# transponder-10_9_0.net
KiCad netlist of a schematic drawn in EAGLE
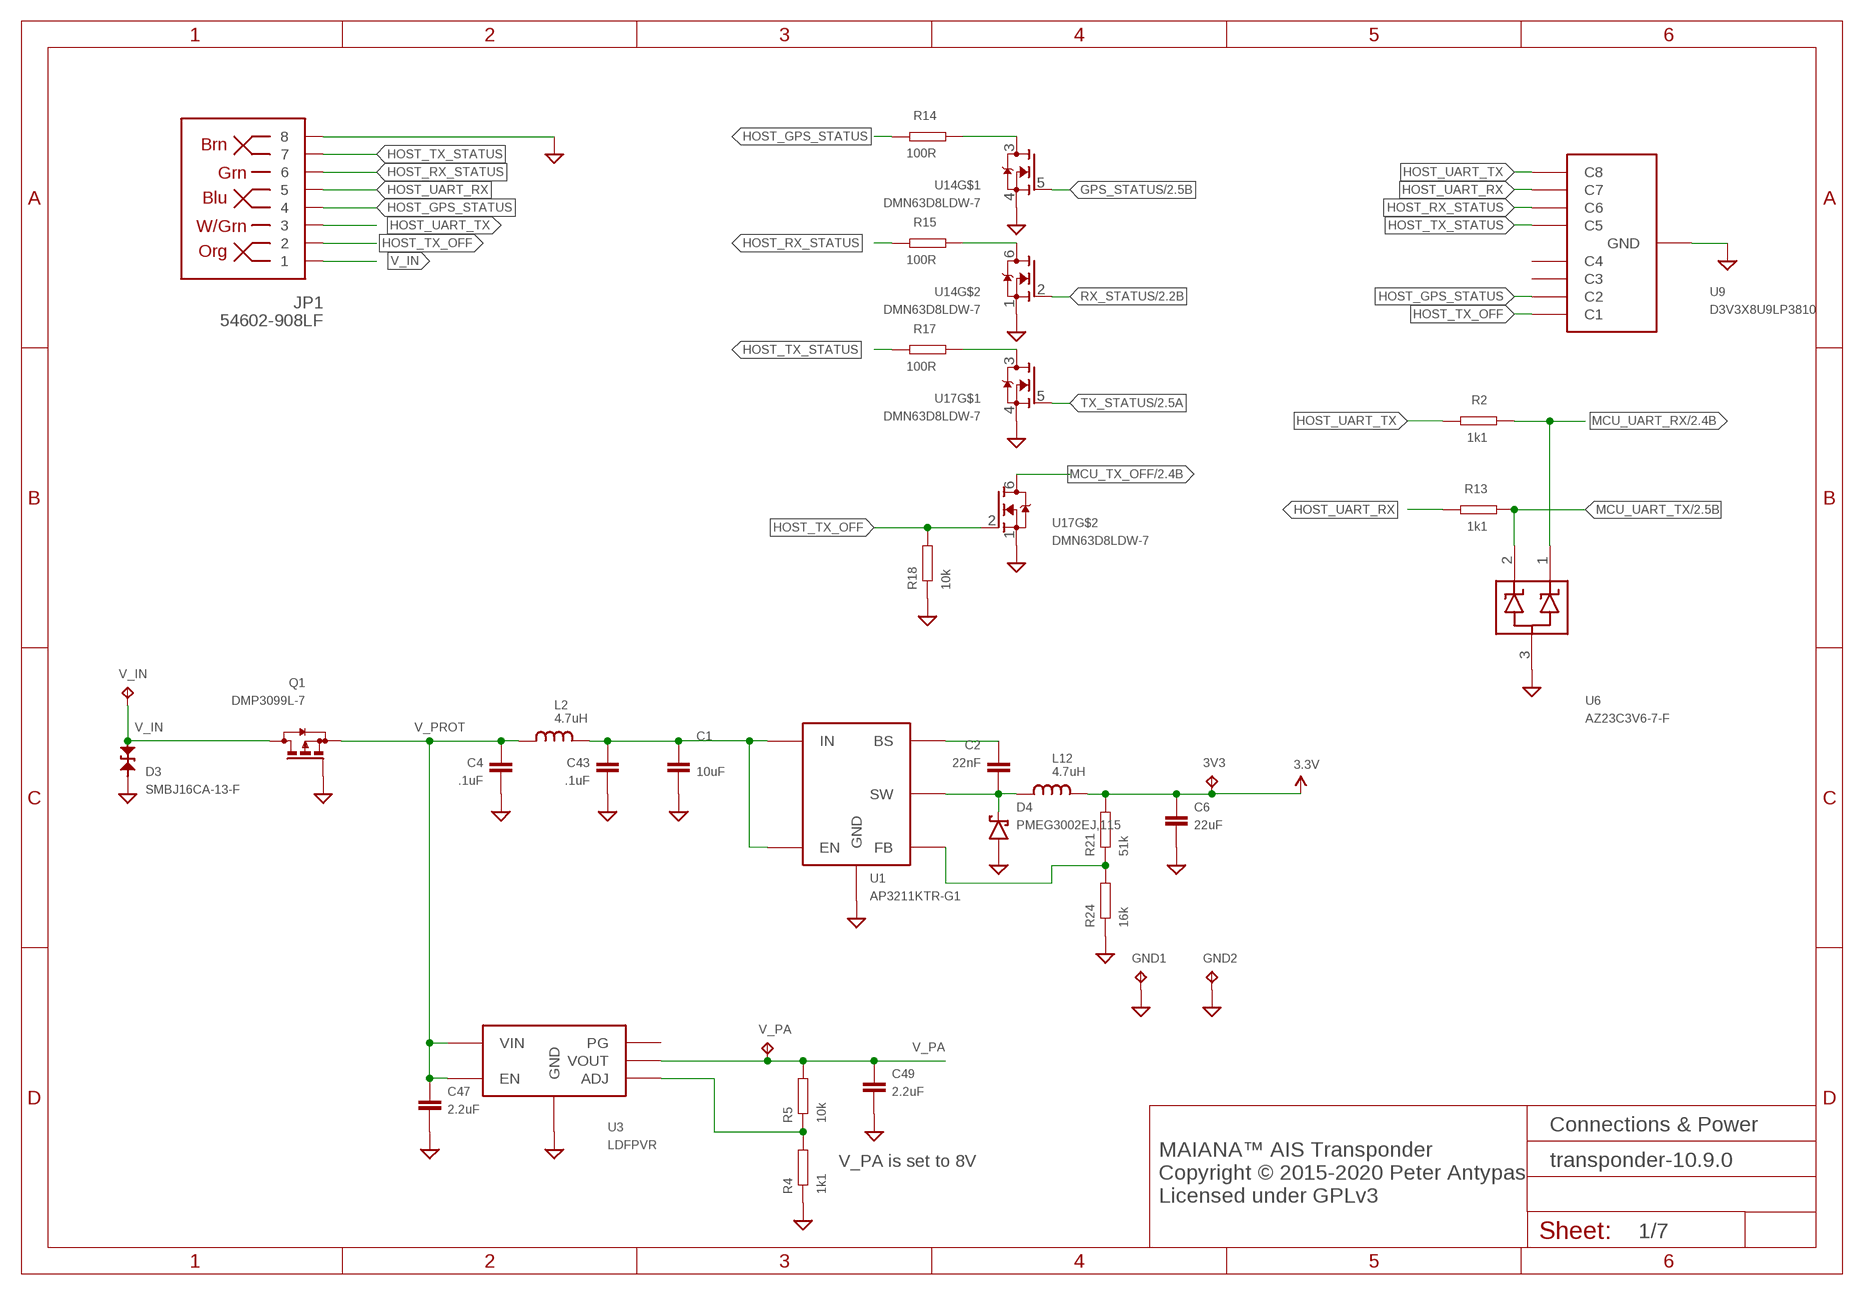
[diagram p0: schematic, sheet 1]
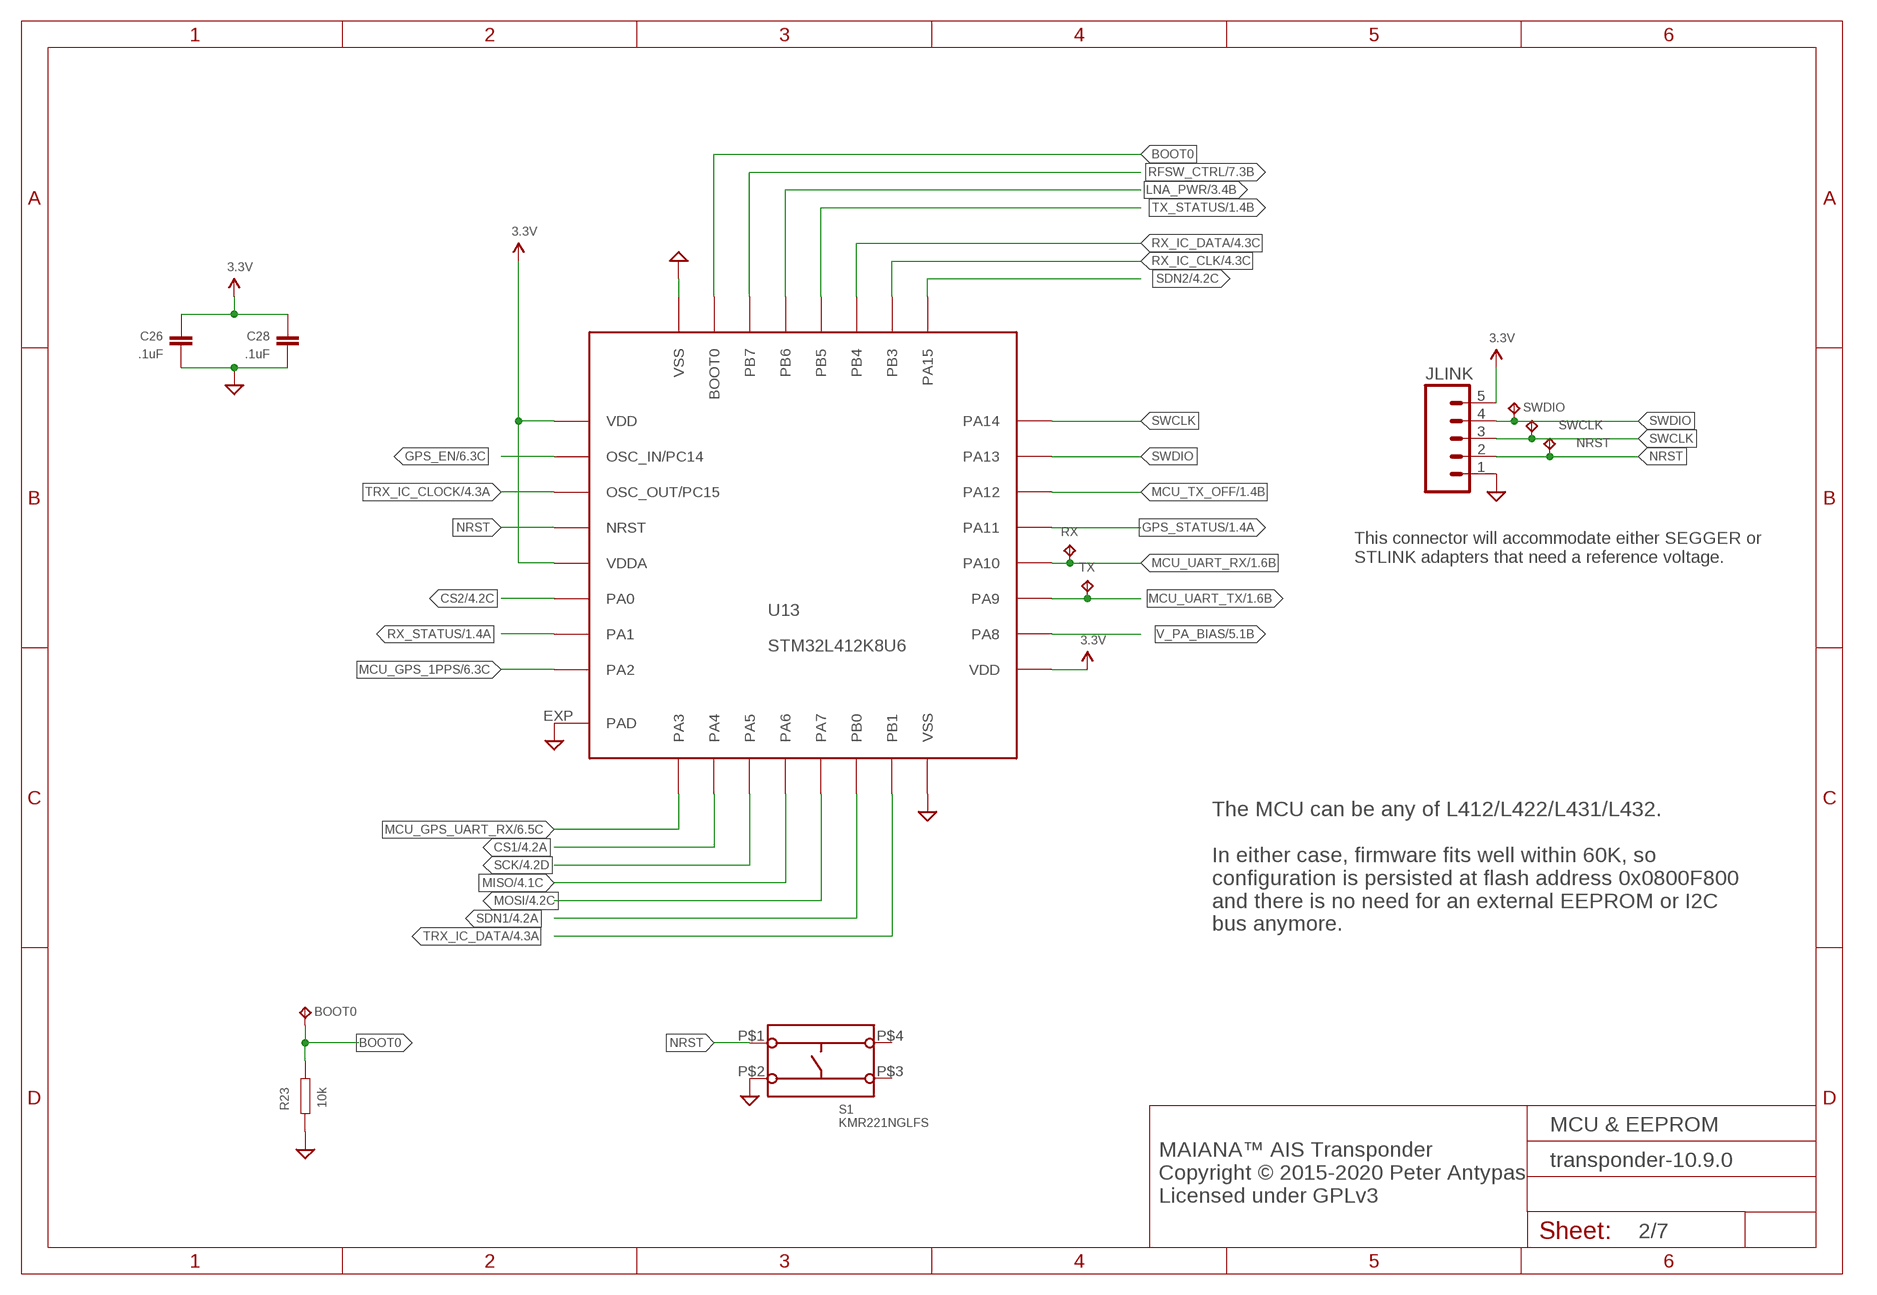
[diagram p1: schematic, sheet 2]
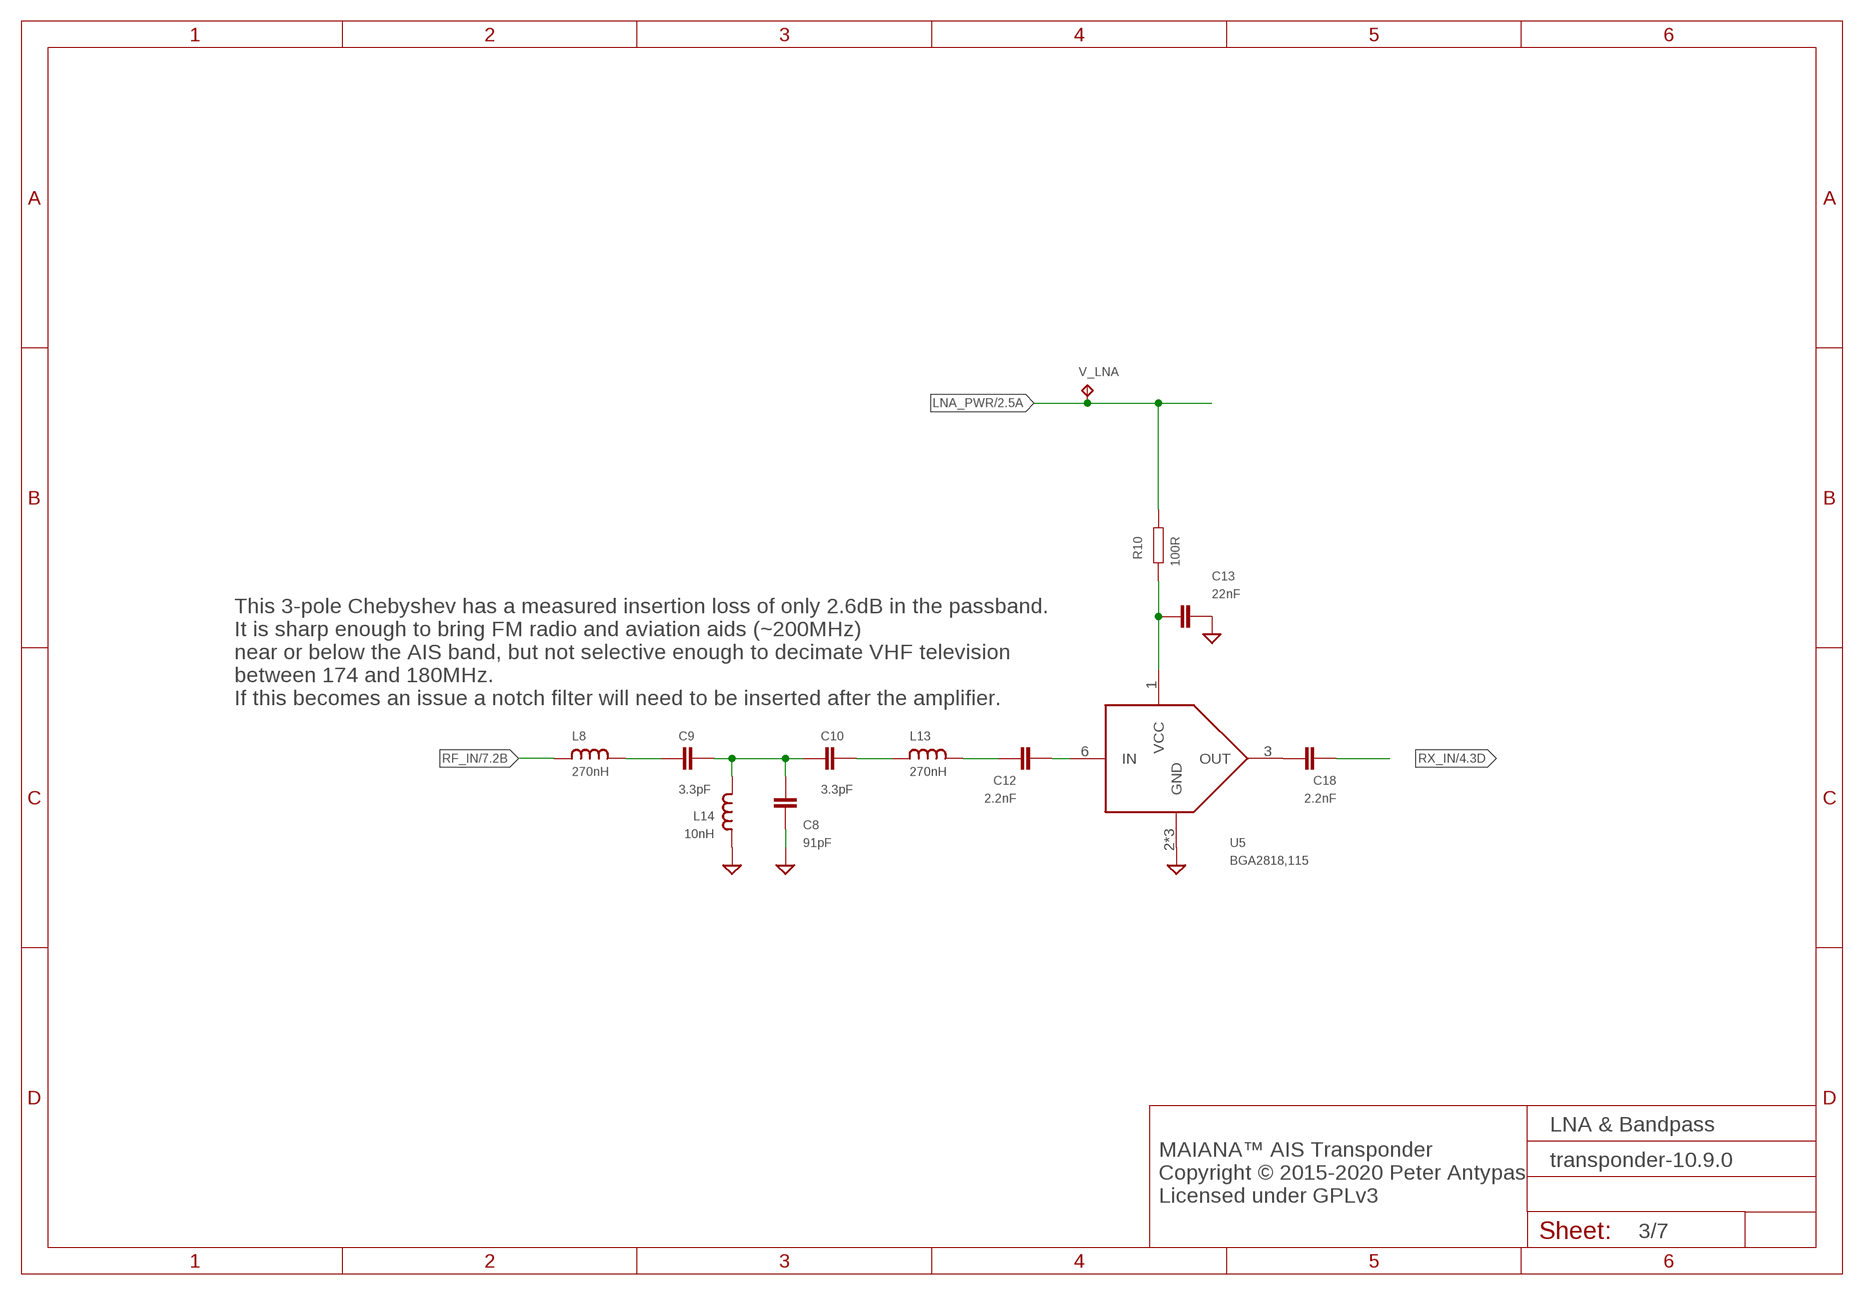
[diagram p2: schematic, sheet 3]
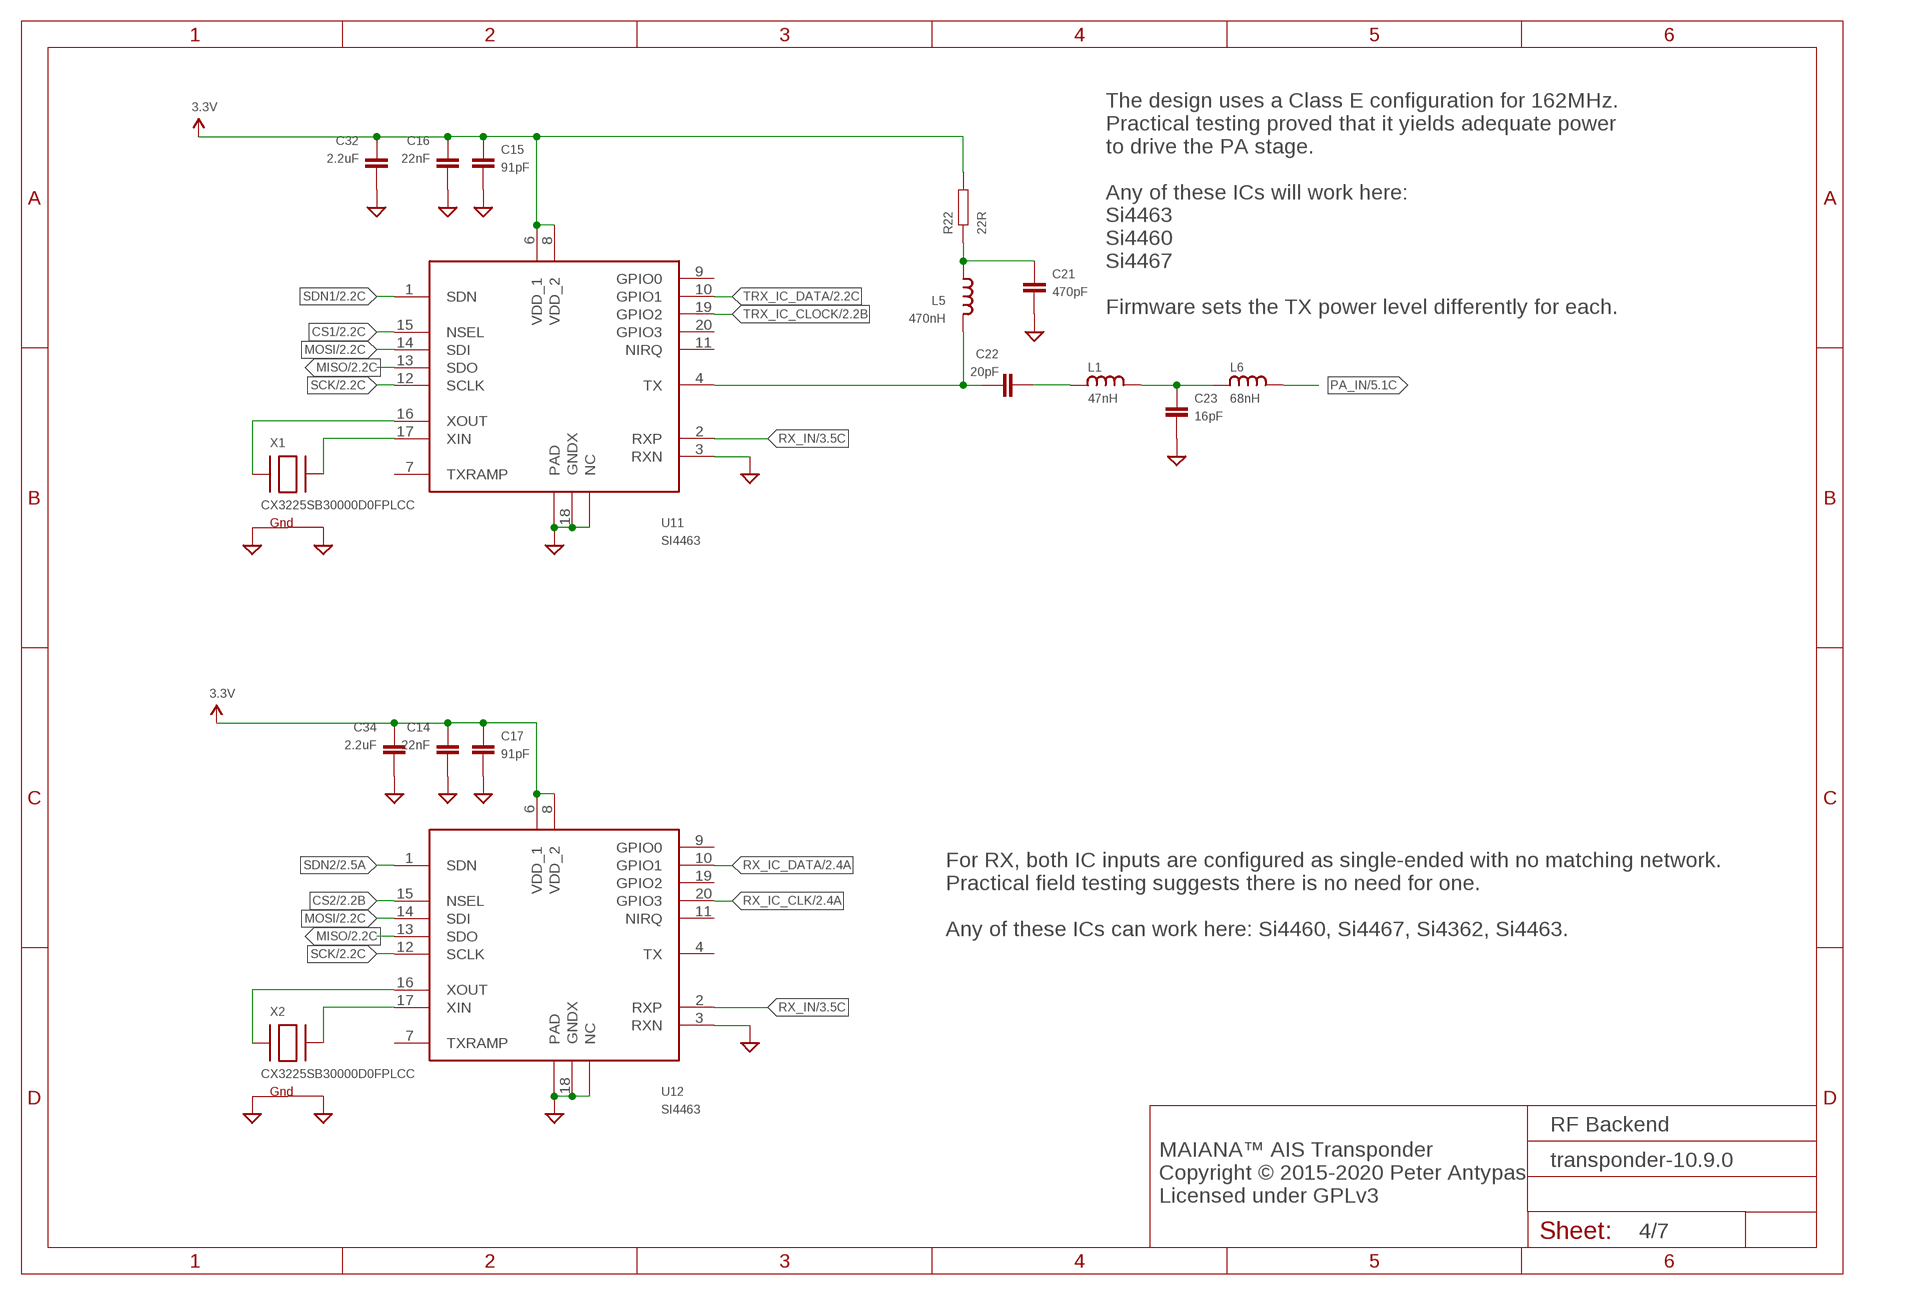
[diagram p3: schematic, sheet 4]
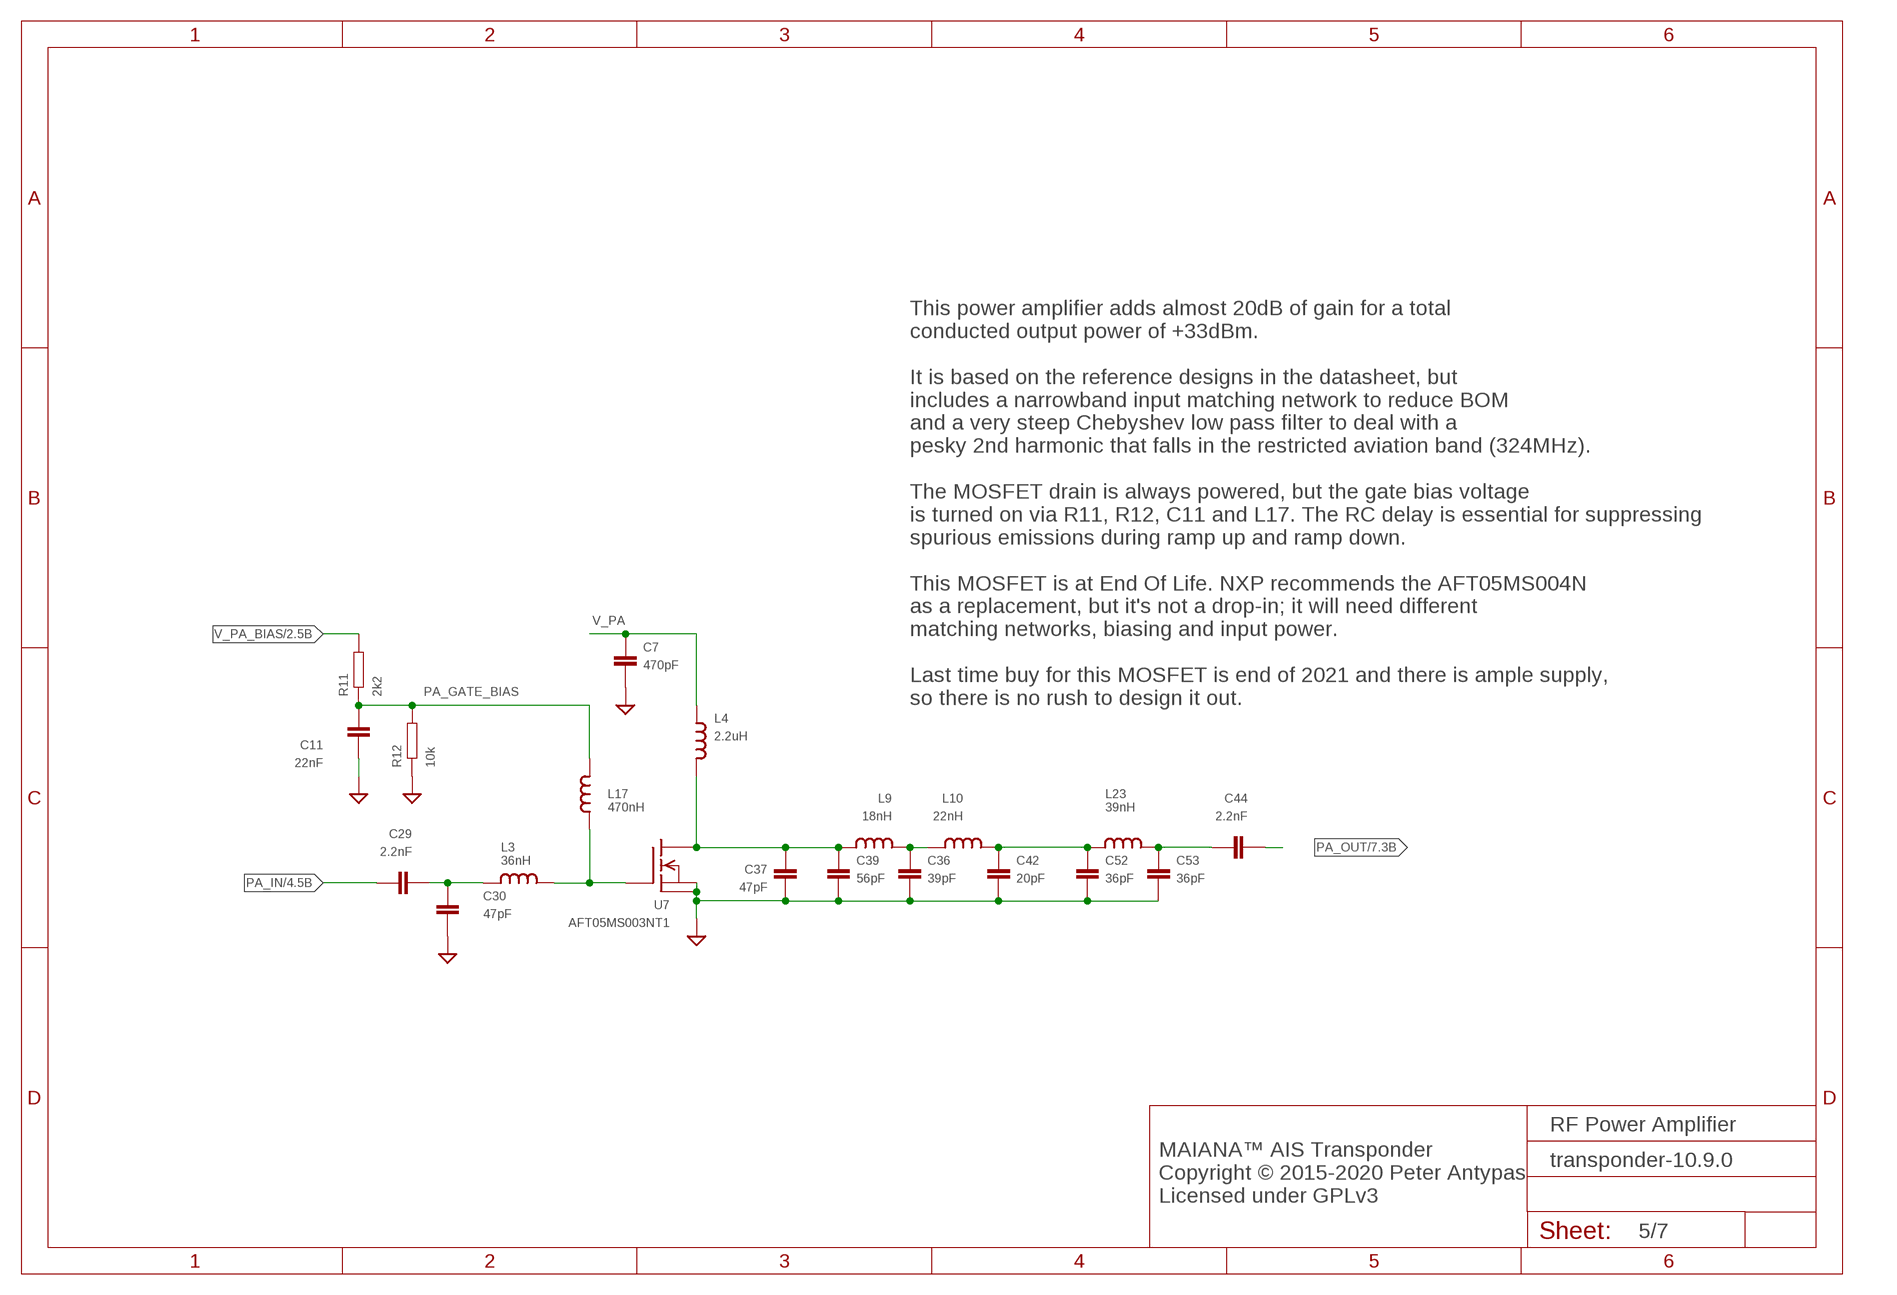
[diagram p4: schematic, sheet 5]
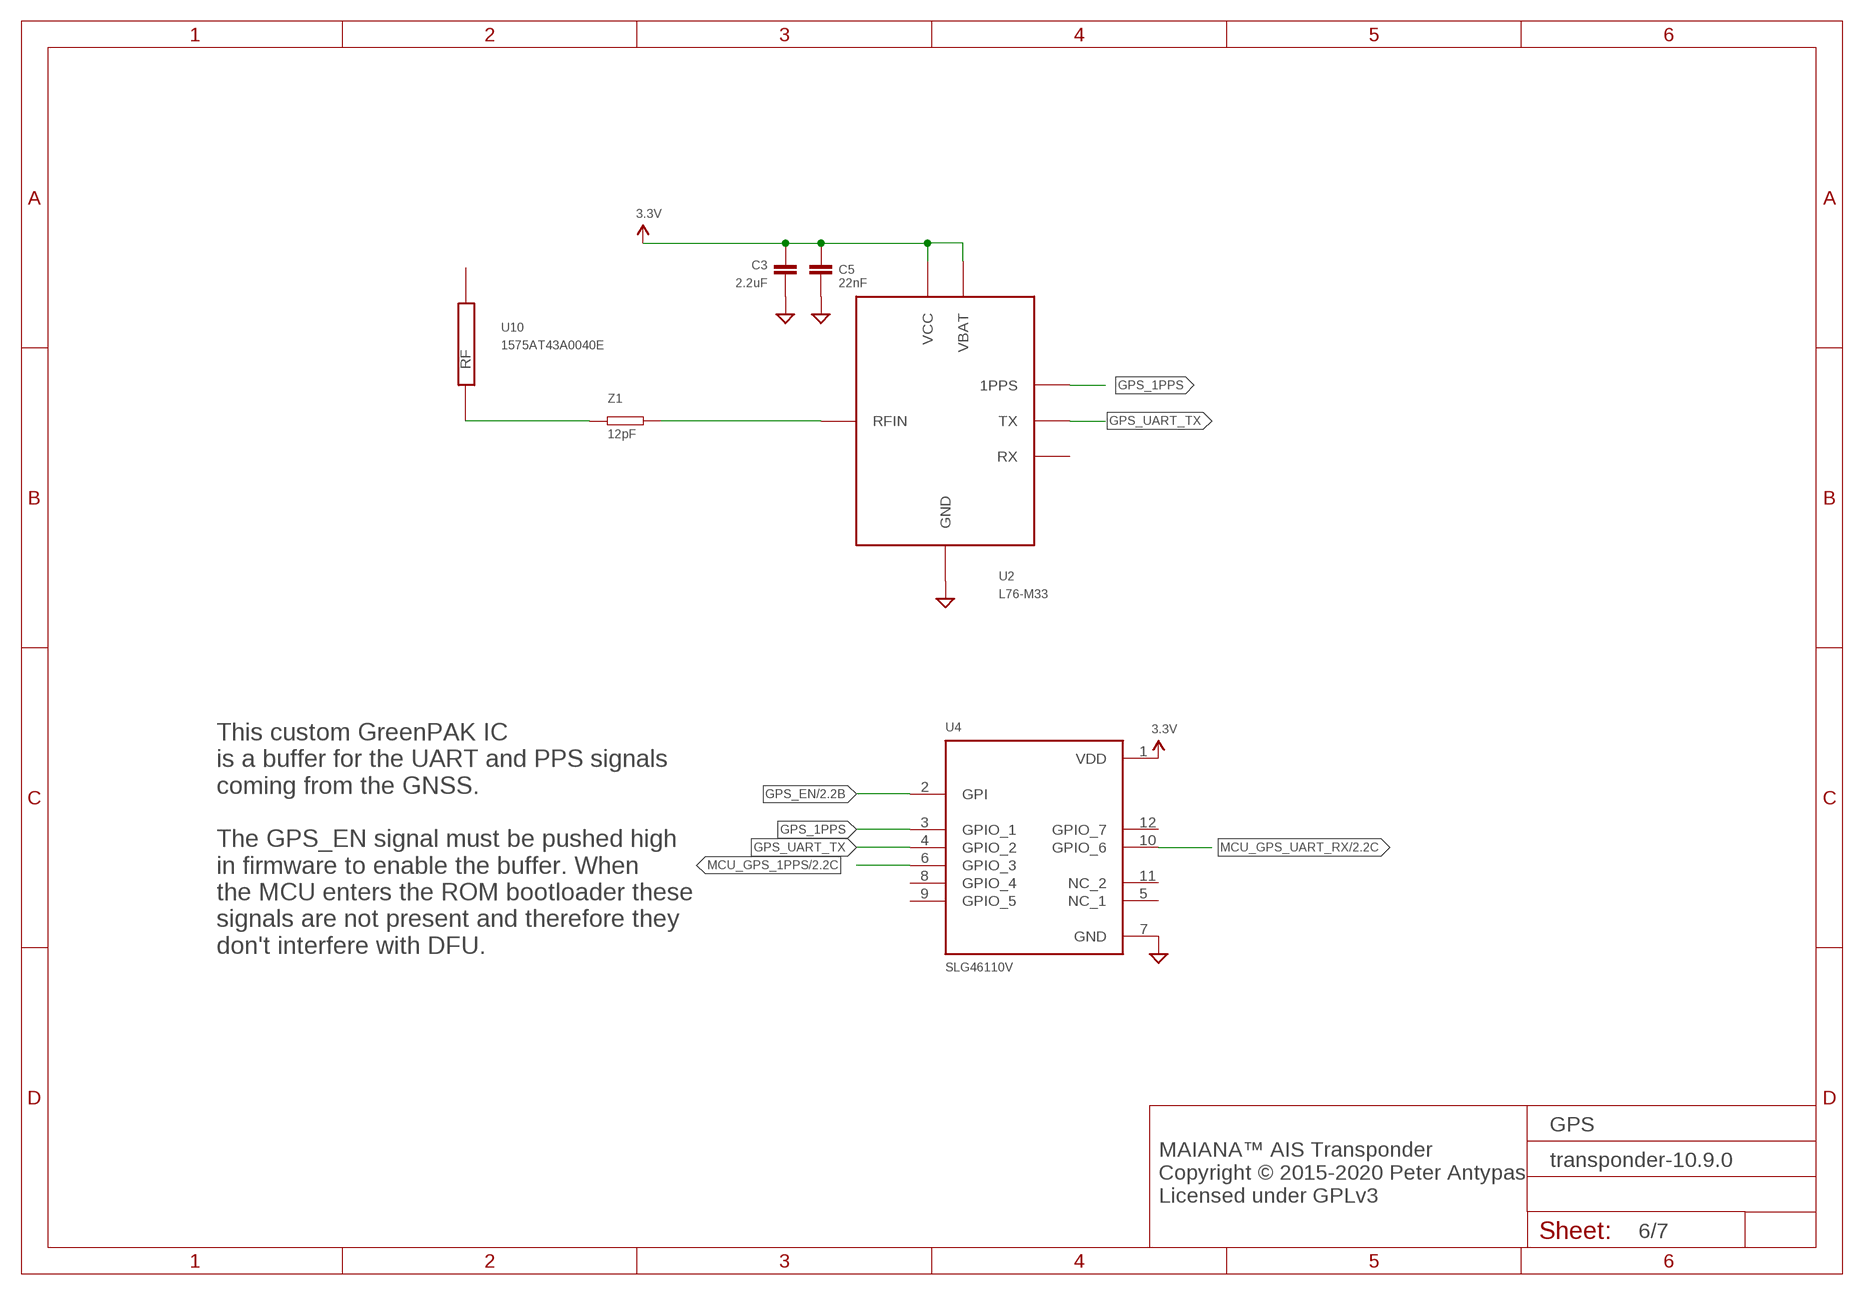
[diagram p5: schematic, sheet 6]
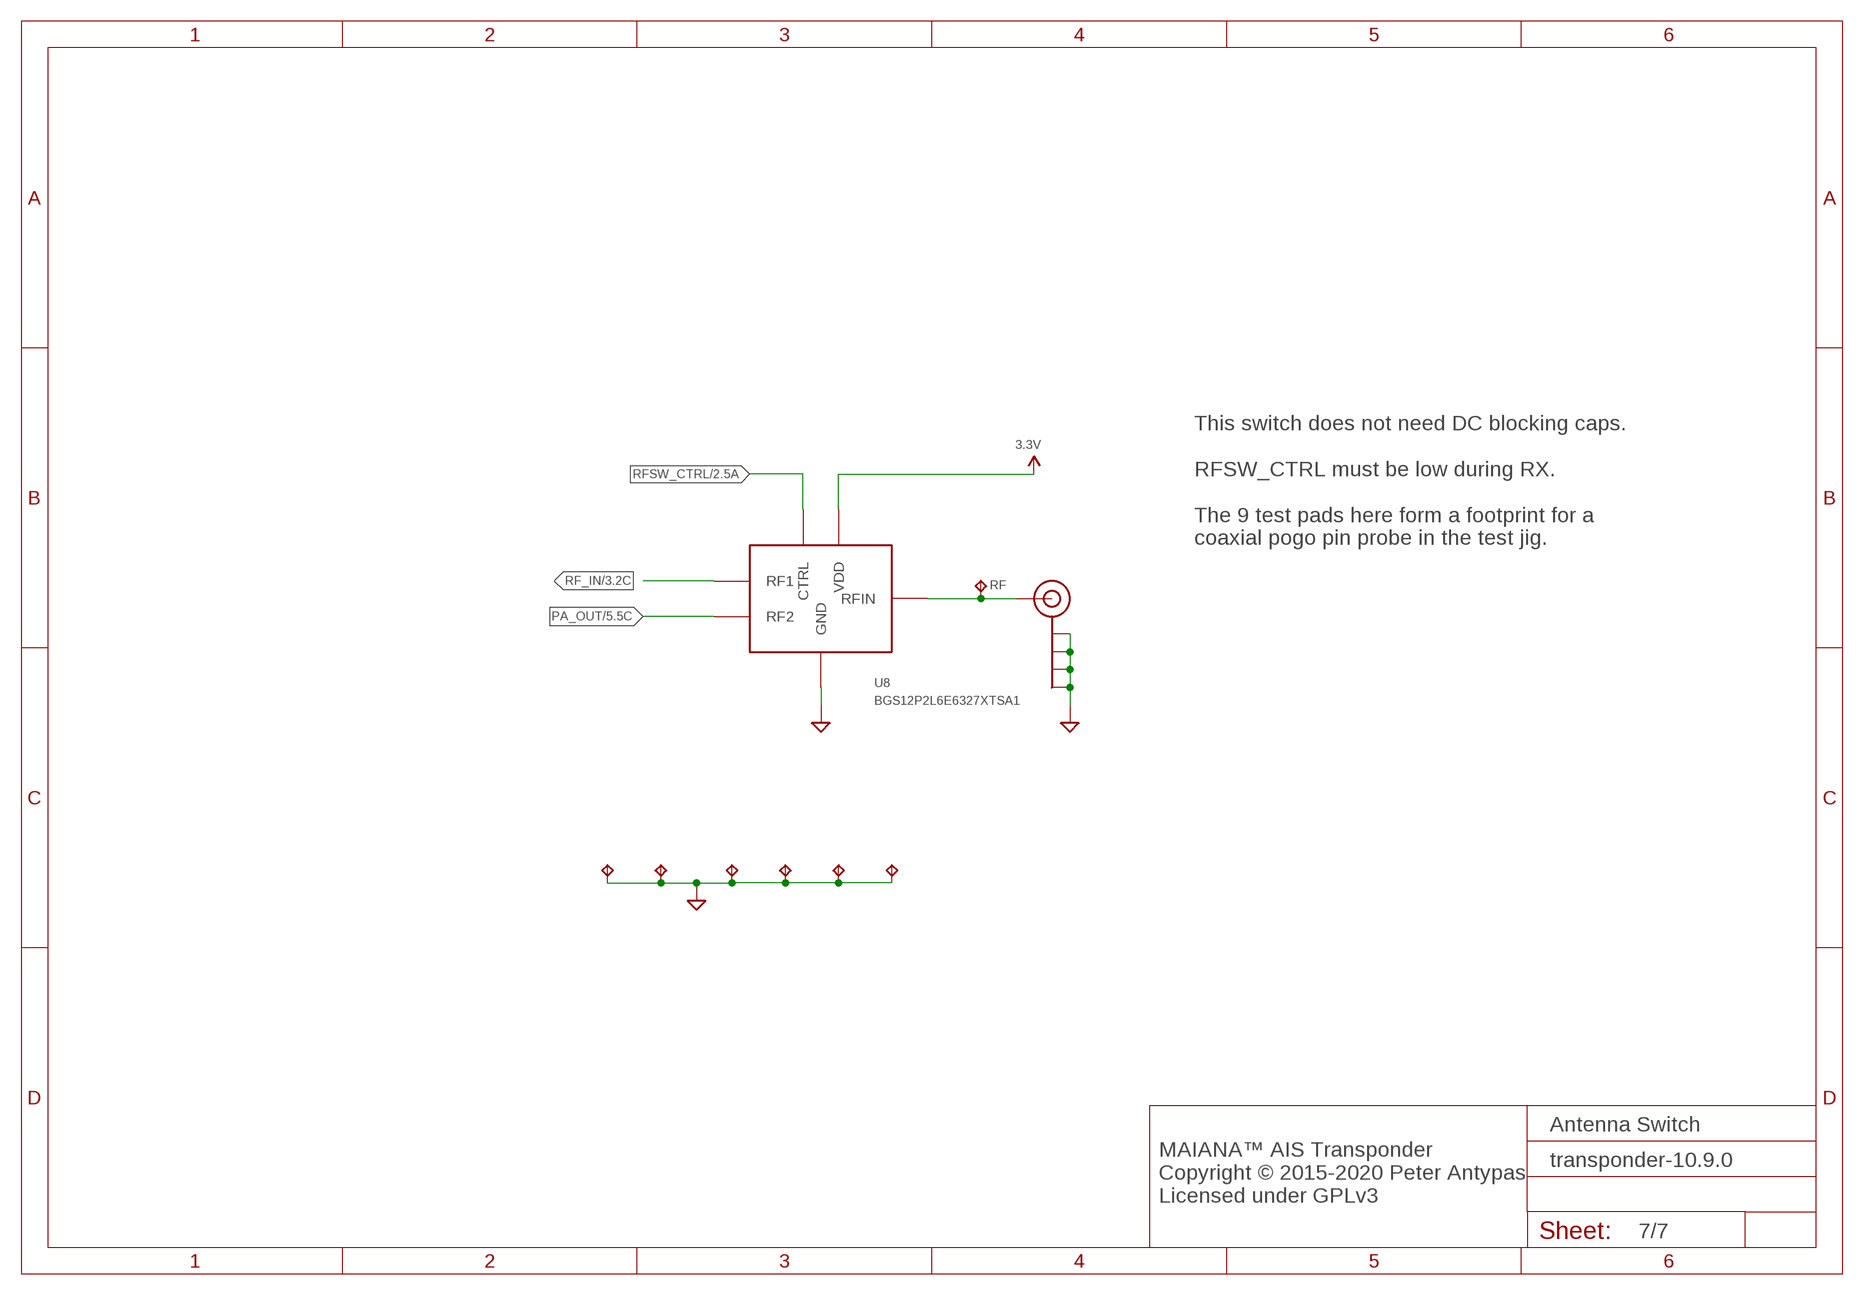
[diagram p6: schematic, sheet 7]

(export (version "E")
  (design (tool "Eeschema 10.0.6"))
  (components
    (comp (ref "BOOT0")
      (value "TPTP12R")
      (footprint "eagle-import:TP12R")
      (libsource (lib "eagle-import") (part "TPTP12R"))
    )
    (comp (ref "C26")
      (value ".1uF")
      (footprint "eagle-import:0603")
      (fields (field (name "PARTNO") "EMK107B7104KAHT"))
      (libsource (lib "eagle-import") (part "CAPACITOR0603"))
    )
    (comp (ref "C28")
      (value ".1uF")
      (footprint "eagle-import:0603")
      (fields (field (name "PARTNO") "EMK107B7104KAHT"))
      (libsource (lib "eagle-import") (part "CAPACITOR0603"))
    )
    (comp (ref "JLINK")
      (value "M05PTH")
      (footprint "eagle-import:1X05")
      (libsource (lib "eagle-import") (part "M05PTH"))
    )
    (comp (ref "NRST")
      (value "TPTP12R")
      (footprint "eagle-import:TP12R")
      (libsource (lib "eagle-import") (part "TPTP12R"))
    )
    (comp (ref "R23")
      (value "10k")
      (footprint "eagle-import:0603")
      (fields (field (name "PARTNO") "RC0603JR-0710KL"))
      (libsource (lib "eagle-import") (part "RESISTOR0603"))
    )
    (comp (ref "RX")
      (value "TPTP12R")
      (footprint "eagle-import:TP12R")
      (libsource (lib "eagle-import") (part "TPTP12R"))
    )
    (comp (ref "S1")
      (value "KMR221NGLFS")
      (footprint "eagle-import:KMR221NGLFS")
      (libsource (lib "eagle-import") (part "KMR221NGLFS"))
    )
    (comp (ref "SWCLK")
      (value "TPTP12R")
      (footprint "eagle-import:TP12R")
      (libsource (lib "eagle-import") (part "TPTP12R"))
    )
    (comp (ref "SWDIO")
      (value "TPTP12R")
      (footprint "eagle-import:TP12R")
      (libsource (lib "eagle-import") (part "TPTP12R"))
    )
    (comp (ref "TX")
      (value "TPTP12R")
      (footprint "eagle-import:TP12R")
      (libsource (lib "eagle-import") (part "TPTP12R"))
    )
    (comp (ref "U13")
      (value "STM32L412K8U6")
      (footprint "eagle-import:QFN32")
      (libsource (lib "eagle-import") (part "STM32L432KXXX"))
    )
    (comp (ref "3V3")
      (value "TPTP12R")
      (footprint "eagle-import:TP12R")
      (libsource (lib "eagle-import") (part "TPTP12R"))
    )
    (comp (ref "C1")
      (value "10uF")
      (footprint "eagle-import:0805")
      (fields (field (name "PARTNO") "EMK212ABJ106KG-T"))
      (libsource (lib "eagle-import") (part "CAPACITOR0805"))
    )
    (comp (ref "C2")
      (value "22nF")
      (footprint "eagle-import:0603")
      (fields (field (name "PARTNO") "GRM188R71E223KA01D"))
      (libsource (lib "eagle-import") (part "CAPACITOR0603"))
    )
    (comp (ref "C4")
      (value ".1uF")
      (footprint "eagle-import:0603")
      (fields (field (name "PARTNO") "EMK107B7104KAHT"))
      (libsource (lib "eagle-import") (part "CAPACITOR0603"))
    )
    (comp (ref "C6")
      (value "22uF")
      (footprint "eagle-import:0805")
      (libsource (lib "eagle-import") (part "CAPACITOR0805"))
    )
    (comp (ref "C43")
      (value ".1uF")
      (footprint "eagle-import:0603")
      (fields (field (name "PARTNO") "EMK107B7104KAHT"))
      (libsource (lib "eagle-import") (part "CAPACITOR0603"))
    )
    (comp (ref "C47")
      (value "2.2uF")
      (footprint "eagle-import:0603")
      (fields (field (name "PARTNO") "EMK107BJ225KA-T"))
      (libsource (lib "eagle-import") (part "CAPACITOR0603"))
    )
    (comp (ref "C49")
      (value "2.2uF")
      (footprint "eagle-import:0603")
      (fields (field (name "PARTNO") "EMK107BJ225KA-T"))
      (libsource (lib "eagle-import") (part "CAPACITOR0603"))
    )
    (comp (ref "D3")
      (value "SMBJ16CA-13-F")
      (footprint "eagle-import:SMB-BIDIR")
      (fields (field (name "PARTNO") "SMBJ16CA-13-F"))
      (libsource (lib "eagle-import") (part "DIODE-TVS-BIDIRSMB"))
    )
    (comp (ref "D4")
      (value "PMEG3002EJ,115")
      (footprint "eagle-import:SOD323")
      (fields (field (name "PARTNO") "NSR0240HT1G"))
      (libsource (lib "eagle-import") (part "DIODE-SCHOTTKYSOD323"))
    )
    (comp (ref "GND1")
      (value "TPTP12R")
      (footprint "eagle-import:TP12R")
      (libsource (lib "eagle-import") (part "TPTP12R"))
    )
    (comp (ref "GND2")
      (value "TPTP12R")
      (footprint "eagle-import:TP12R")
      (libsource (lib "eagle-import") (part "TPTP12R"))
    )
    (comp (ref "JP1")
      (value "54602-908LF")
      (footprint "eagle-import:RJ45-8")
      (fields (field (name "PARTNO") "54602-908LF‎"))
      (libsource (lib "eagle-import") (part "RJ45-8PTH"))
    )
    (comp (ref "L2")
      (value "4.7uH")
      (footprint "eagle-import:0805")
      (fields (field (name "PARTNO") "MLZ2012M4R7WT000"))
      (libsource (lib "eagle-import") (part "INDUCTOR0805"))
    )
    (comp (ref "L12")
      (value "4.7uH")
      (footprint "eagle-import:0805")
      (fields (field (name "PARTNO") "MLZ2012M4R7WT000"))
      (libsource (lib "eagle-import") (part "INDUCTOR0805"))
    )
    (comp (ref "Q1")
      (value "DMP3099L-7")
      (footprint "eagle-import:SOT23")
      (libsource (lib "eagle-import") (part "BSS84"))
    )
    (comp (ref "R2")
      (value "1k1")
      (footprint "eagle-import:0603")
      (fields (field (name "PARTNO") "RC0603JR-071K1L"))
      (libsource (lib "eagle-import") (part "RESISTOR0603"))
    )
    (comp (ref "R4")
      (value "1k1")
      (footprint "eagle-import:0603")
      (fields (field (name "PARTNO") "RC0603JR-071K1L"))
      (libsource (lib "eagle-import") (part "RESISTOR0603"))
    )
    (comp (ref "R5")
      (value "10k")
      (footprint "eagle-import:0603")
      (fields (field (name "PARTNO") "RC0603JR-0710KL"))
      (libsource (lib "eagle-import") (part "RESISTOR0603"))
    )
    (comp (ref "R13")
      (value "1k1")
      (footprint "eagle-import:0603")
      (fields (field (name "PARTNO") "RC0603JR-071K1L"))
      (libsource (lib "eagle-import") (part "RESISTOR0603"))
    )
    (comp (ref "R14")
      (value "100R")
      (footprint "eagle-import:0603")
      (fields (field (name "PARTNO") "RC0603JR-07100RL"))
      (libsource (lib "eagle-import") (part "RESISTOR0603"))
    )
    (comp (ref "R15")
      (value "100R")
      (footprint "eagle-import:0603")
      (fields (field (name "PARTNO") "RC0603JR-07100RL"))
      (libsource (lib "eagle-import") (part "RESISTOR0603"))
    )
    (comp (ref "R17")
      (value "100R")
      (footprint "eagle-import:0603")
      (fields (field (name "PARTNO") "RC0603JR-070RL"))
      (libsource (lib "eagle-import") (part "RESISTOR0603"))
    )
    (comp (ref "R18")
      (value "10k")
      (footprint "eagle-import:0603")
      (fields (field (name "PARTNO") "RC0603JR-0710KL"))
      (libsource (lib "eagle-import") (part "RESISTOR0603"))
    )
    (comp (ref "R21")
      (value "51k")
      (footprint "eagle-import:0603")
      (fields (field (name "PARTNO") "RC0603JR-0751KL"))
      (libsource (lib "eagle-import") (part "RESISTOR0603"))
    )
    (comp (ref "R24")
      (value "16k")
      (footprint "eagle-import:0603")
      (fields (field (name "PARTNO") "RC0603FR-1016KL"))
      (libsource (lib "eagle-import") (part "RESISTOR0603"))
    )
    (comp (ref "U1")
      (value "AP3211KTR-G1")
      (footprint "eagle-import:SOT23-6")
      (libsource (lib "eagle-import") (part "AP3211"))
    )
    (comp (ref "U3")
      (value "LDFPVR")
      (footprint "eagle-import:DFN6-2X2")
      (fields (field (name "PARTNO") "LDFPUR"))
      (libsource (lib "eagle-import") (part "LDFPVR"))
    )
    (comp (ref "U6")
      (value "AZ23C3V6-7-F")
      (footprint "eagle-import:SOT-23")
      (libsource (lib "eagle-import") (part "AZ23C3V6-7-F"))
    )
    (comp (ref "U9")
      (value "D3V3X8U9LP3810")
      (footprint "eagle-import:U-DFN3810-9(B)")
      (libsource (lib "eagle-import") (part "D3V3X8U9LP3810"))
    )
    (comp (ref "U14")
      (value "DMN63D8LDW-7")
      (footprint "eagle-import:SOT363")
      (fields (field (name "PARTNO") "DMN63D8LDW-7"))
      (libsource (lib "eagle-import") (part "DMN63D8LDW"))
    )
    (comp (ref "U17")
      (value "DMN63D8LDW-7")
      (footprint "eagle-import:SOT363")
      (fields (field (name "PARTNO") "DMN63D8LDW-7"))
      (libsource (lib "eagle-import") (part "DMN63D8LDW"))
    )
    (comp (ref "V_IN")
      (value "TPTP12R")
      (footprint "eagle-import:TP12R")
      (libsource (lib "eagle-import") (part "TPTP12R"))
    )
    (comp (ref "V_PA")
      (value "TPTP12R")
      (footprint "eagle-import:TP12R")
      (libsource (lib "eagle-import") (part "TPTP12R"))
    )
    (comp (ref "C14")
      (value "22nF")
      (footprint "eagle-import:0603")
      (fields (field (name "PARTNO") "GRM188R71E223KA01D"))
      (libsource (lib "eagle-import") (part "CAPACITOR0603"))
    )
    (comp (ref "C15")
      (value "91pF")
      (footprint "eagle-import:0603")
      (fields (field (name "PARTNO") "GRM1885C2A910JA01D"))
      (libsource (lib "eagle-import") (part "CAPACITOR0603"))
    )
    (comp (ref "C16")
      (value "22nF")
      (footprint "eagle-import:0603")
      (fields (field (name "PARTNO") "GRM188R71E223KA01D"))
      (libsource (lib "eagle-import") (part "CAPACITOR0603"))
    )
    (comp (ref "C17")
      (value "91pF")
      (footprint "eagle-import:0603")
      (fields (field (name "PARTNO") "GRM1885C2A910JA01D"))
      (libsource (lib "eagle-import") (part "CAPACITOR0603"))
    )
    (comp (ref "C21")
      (value "470pF")
      (footprint "eagle-import:0603")
      (fields (field (name "PARTNO") "GRM1885C1H471JA01D"))
      (libsource (lib "eagle-import") (part "CAPACITOR0603"))
    )
    (comp (ref "C22")
      (value "20pF")
      (footprint "eagle-import:0603")
      (fields (field (name "PARTNO") "GRM1885C1H200JA01D"))
      (libsource (lib "eagle-import") (part "CAPACITOR0603"))
    )
    (comp (ref "C23")
      (value "16pF")
      (footprint "eagle-import:0603")
      (fields (field (name "PARTNO") "GCM1885C2A160JA16D"))
      (libsource (lib "eagle-import") (part "CAPACITOR0603"))
    )
    (comp (ref "C32")
      (value "2.2uF")
      (footprint "eagle-import:0603")
      (fields (field (name "PARTNO") "EMK107BJ225KA-T"))
      (libsource (lib "eagle-import") (part "CAPACITOR0603"))
    )
    (comp (ref "C34")
      (value "2.2uF")
      (footprint "eagle-import:0603")
      (fields (field (name "PARTNO") "EMK107BJ225KA-T"))
      (libsource (lib "eagle-import") (part "CAPACITOR0603"))
    )
    (comp (ref "L1")
      (value "47nH")
      (footprint "eagle-import:0603")
      (fields (field (name "PARTNO") "LQW18AN47NG00D"))
      (libsource (lib "eagle-import") (part "INDUCTOR0603"))
    )
    (comp (ref "L5")
      (value "470nH")
      (footprint "eagle-import:0603")
      (fields (field (name "PARTNO") "HK1608R47J-T"))
      (libsource (lib "eagle-import") (part "INDUCTOR0603"))
    )
    (comp (ref "L6")
      (value "68nH")
      (footprint "eagle-import:0603")
      (libsource (lib "eagle-import") (part "INDUCTOR0603"))
    )
    (comp (ref "R22")
      (value "22R")
      (footprint "eagle-import:0603")
      (fields (field (name "PARTNO") "RC0603JR-0722RL"))
      (libsource (lib "eagle-import") (part "RESISTOR0603"))
    )
    (comp (ref "U11")
      (value "SI4463")
      (footprint "eagle-import:SI4463")
      (fields (field (name "PARTNO") "SI4463-C2A-GMR"))
      (libsource (lib "eagle-import") (part "SI4463"))
    )
    (comp (ref "U12")
      (value "SI4463")
      (footprint "eagle-import:SI4463")
      (fields (field (name "PARTNO") "SI4463-C2A-GMR"))
      (libsource (lib "eagle-import") (part "SI4463"))
    )
    (comp (ref "X1")
      (value "CX3225SB30000D0FPLCC")
      (footprint "eagle-import:NX3225")
      (libsource (lib "eagle-import") (part "XTAL-4-3225"))
    )
    (comp (ref "X2")
      (value "CX3225SB30000D0FPLCC")
      (footprint "eagle-import:NX3225")
      (libsource (lib "eagle-import") (part "XTAL-4-3225"))
    )
    (comp (ref "C8")
      (value "91pF")
      (footprint "eagle-import:0603")
      (fields (field (name "PARTNO") "GRM1885C2A910JA01D"))
      (libsource (lib "eagle-import") (part "CAPACITOR0603"))
    )
    (comp (ref "C9")
      (value "3.3pF")
      (footprint "eagle-import:0603")
      (fields (field (name "PARTNO") "GRM1885C1H3R3BA01D"))
      (libsource (lib "eagle-import") (part "CAPACITOR0603"))
    )
    (comp (ref "C10")
      (value "3.3pF")
      (footprint "eagle-import:0603")
      (fields (field (name "PARTNO") "GRM1885C1H3R3BA01D"))
      (libsource (lib "eagle-import") (part "CAPACITOR0603"))
    )
    (comp (ref "C12")
      (value "2.2nF")
      (footprint "eagle-import:0603")
      (fields (field (name "PARTNO") "GRM1885C1H222JA01J"))
      (libsource (lib "eagle-import") (part "CAPACITOR0603"))
    )
    (comp (ref "C13")
      (value "22nF")
      (footprint "eagle-import:0603")
      (fields (field (name "PARTNO") "GRM188R71E223KA01D"))
      (libsource (lib "eagle-import") (part "CAPACITOR0603"))
    )
    (comp (ref "C18")
      (value "2.2nF")
      (footprint "eagle-import:0603")
      (fields (field (name "PARTNO") "GRM1885C1H222JA01J"))
      (libsource (lib "eagle-import") (part "CAPACITOR0603"))
    )
    (comp (ref "L8")
      (value "270nH")
      (footprint "eagle-import:0603")
      (fields (field (name "PARTNO") "LQW18ANR27J00D"))
      (libsource (lib "eagle-import") (part "INDUCTOR0603"))
    )
    (comp (ref "L13")
      (value "270nH")
      (footprint "eagle-import:0603")
      (fields (field (name "PARTNO") "LQW18ANR27J00D"))
      (libsource (lib "eagle-import") (part "INDUCTOR0603"))
    )
    (comp (ref "L14")
      (value "10nH")
      (footprint "eagle-import:0603")
      (fields (field (name "PARTNO") "LQW18AN10NG00D"))
      (libsource (lib "eagle-import") (part "INDUCTOR0603"))
    )
    (comp (ref "R10")
      (value "100R")
      (footprint "eagle-import:0603")
      (fields (field (name "PARTNO") "RC0603JR-07100RL"))
      (libsource (lib "eagle-import") (part "RESISTOR0603"))
    )
    (comp (ref "U5")
      (value "BGA2818,115")
      (footprint "eagle-import:SOT363")
      (libsource (lib "eagle-import") (part "BGA2870"))
    )
    (comp (ref "V_LNA")
      (value "TPTP12R")
      (footprint "eagle-import:TP12R")
      (libsource (lib "eagle-import") (part "TPTP12R"))
    )
    (comp (ref "C3")
      (value "2.2uF")
      (footprint "eagle-import:0603")
      (fields (field (name "PARTNO") "EMK107BJ225KA-T"))
      (libsource (lib "eagle-import") (part "CAPACITOR0603"))
    )
    (comp (ref "C5")
      (value "22nF")
      (footprint "eagle-import:0603")
      (fields (field (name "PARTNO") "GRM188R71E223KA01D"))
      (libsource (lib "eagle-import") (part "CAPACITOR0603"))
    )
    (comp (ref "U2")
      (value "L76-M33")
      (footprint "eagle-import:GPS_MODULE")
      (fields (field (name "PARTNO") "L70B-M39"))
      (libsource (lib "eagle-import") (part "L70"))
    )
    (comp (ref "U4")
      (value "SLG46110V")
      (footprint "eagle-import:IC_SLG46110V")
      (fields (field (name "MF") "Dialog Semiconductor GmbH"))
      (libsource (lib "eagle-import") (part "SLG46110V"))
    )
    (comp (ref "U10")
      (value "1575AT43A0040E")
      (footprint "eagle-import:1575AT43A0040E")
      (libsource (lib "eagle-import") (part "1575AT43A0040E"))
    )
    (comp (ref "Z1")
      (value "12pF")
      (footprint "eagle-import:0603")
      (fields (field (name "PARTNO") "‎GRM1885C1H120GA01D‎"))
      (libsource (lib "eagle-import") (part "RESISTOR0603"))
    )
    (comp (ref "J$1")
      (value "SMA_EDGE")
      (footprint "eagle-import:SMA-EDGE")
      (libsource (lib "eagle-import") (part "SMA_EDGE"))
    )
    (comp (ref "RF")
      (value "TPTP10R")
      (footprint "eagle-import:TP10R")
      (libsource (lib "eagle-import") (part "TPTP10R"))
    )
    (comp (ref "SWDIO1")
      (value "TPTP12R")
      (footprint "eagle-import:TP12R")
      (libsource (lib "eagle-import") (part "TPTP12R"))
    )
    (comp (ref "SWDIO2")
      (value "TPTP12R")
      (footprint "eagle-import:TP12R")
      (libsource (lib "eagle-import") (part "TPTP12R"))
    )
    (comp (ref "SWDIO3")
      (value "TPTP12R")
      (footprint "eagle-import:TP12R")
      (libsource (lib "eagle-import") (part "TPTP12R"))
    )
    (comp (ref "SWDIO4")
      (value "TPTP12R")
      (footprint "eagle-import:TP12R")
      (libsource (lib "eagle-import") (part "TPTP12R"))
    )
    (comp (ref "SWDIO5")
      (value "TPTP12R")
      (footprint "eagle-import:TP12R")
      (libsource (lib "eagle-import") (part "TPTP12R"))
    )
    (comp (ref "SWDIO6")
      (value "TPTP12R")
      (footprint "eagle-import:TP12R")
      (libsource (lib "eagle-import") (part "TPTP12R"))
    )
    (comp (ref "U8")
      (value "BGS12P2L6E6327XTSA1")
      (footprint "eagle-import:PSON50P145X100X50-6N")
      (fields (field (name "PARTNO") "BGS12PL6") (field (name "PARTNO_1") "‎BGS12P2L6E6327XTSA1‎"))
      (libsource (lib "eagle-import") (part "BGS12PL6"))
    )
    (comp (ref "C7")
      (value "470pF")
      (footprint "eagle-import:0603")
      (fields (field (name "PARTNO") "GRM1885C1H471JA01D"))
      (libsource (lib "eagle-import") (part "CAPACITOR0603"))
    )
    (comp (ref "C11")
      (value "22nF")
      (footprint "eagle-import:0603")
      (fields (field (name "PARTNO") "GRM188R71E223KA01D"))
      (libsource (lib "eagle-import") (part "CAPACITOR0603"))
    )
    (comp (ref "C29")
      (value "2.2nF")
      (footprint "eagle-import:0603")
      (fields (field (name "PARTNO") "GRM1885C1H222JA01J"))
      (libsource (lib "eagle-import") (part "CAPACITOR0603"))
    )
    (comp (ref "C30")
      (value "47pF")
      (footprint "eagle-import:0603")
      (fields (field (name "PARTNO") "GRM1885C1H470JA01J"))
      (libsource (lib "eagle-import") (part "CAPACITOR0603"))
    )
    (comp (ref "C36")
      (value "39pF")
      (footprint "eagle-import:0603")
      (fields (field (name "PARTNO") "GRM1885C1H390JA01D"))
      (libsource (lib "eagle-import") (part "CAPACITOR0603"))
    )
    (comp (ref "C37")
      (value "47pF")
      (footprint "eagle-import:0603")
      (fields (field (name "PARTNO") "GRM1885C1H470JA01J"))
      (libsource (lib "eagle-import") (part "CAPACITOR0603"))
    )
    (comp (ref "C39")
      (value "56pF")
      (footprint "eagle-import:0603")
      (fields (field (name "PARTNO") "GRM1885C1H560JA01D"))
      (libsource (lib "eagle-import") (part "CAPACITOR0603"))
    )
    (comp (ref "C42")
      (value "20pF")
      (footprint "eagle-import:0603")
      (fields (field (name "PARTNO") "GRM1885C1H200JA01D"))
      (libsource (lib "eagle-import") (part "CAPACITOR0603"))
    )
    (comp (ref "C44")
      (value "2.2nF")
      (footprint "eagle-import:0603")
      (fields (field (name "PARTNO") "GRM1885C1H222JA01J"))
      (libsource (lib "eagle-import") (part "CAPACITOR0603"))
    )
    (comp (ref "C52")
      (value "36pF")
      (footprint "eagle-import:0603")
      (fields (field (name "PARTNO") "06035A360JAT2A"))
      (libsource (lib "eagle-import") (part "CAPACITOR0603"))
    )
    (comp (ref "C53")
      (value "36pF")
      (footprint "eagle-import:0603")
      (fields (field (name "PARTNO") "06035A360JAT2A"))
      (libsource (lib "eagle-import") (part "CAPACITOR0603"))
    )
    (comp (ref "L3")
      (value "36nH")
      (footprint "eagle-import:0603")
      (fields (field (name "PARTNO") "LQW18AN36NG00D"))
      (libsource (lib "eagle-import") (part "INDUCTOR0603"))
    )
    (comp (ref "L4")
      (value "2.2uH")
      (footprint "eagle-import:0805")
      (fields (field (name "PARTNO") "BRC2012T2R2MD"))
      (libsource (lib "eagle-import") (part "INDUCTOR0805"))
    )
    (comp (ref "L9")
      (value "18nH")
      (footprint "eagle-import:0603")
      (fields (field (name "PARTNO") "LQW18AN18NG00D"))
      (libsource (lib "eagle-import") (part "INDUCTOR0603"))
    )
    (comp (ref "L10")
      (value "22nH")
      (footprint "eagle-import:0603")
      (fields (field (name "PARTNO") "LQW18AN22NJ00D"))
      (libsource (lib "eagle-import") (part "INDUCTOR0603"))
    )
    (comp (ref "L17")
      (value "470nH")
      (footprint "eagle-import:0603")
      (fields (field (name "PARTNO") "HK1608R47J-T"))
      (libsource (lib "eagle-import") (part "INDUCTOR0603"))
    )
    (comp (ref "L23")
      (value "39nH")
      (footprint "eagle-import:0603")
      (fields (field (name "PARTNO") "LQW18AN39NG00D"))
      (libsource (lib "eagle-import") (part "INDUCTOR0603"))
    )
    (comp (ref "R11")
      (value "2k2")
      (footprint "eagle-import:0603")
      (fields (field (name "PARTNO") "RC0603FR-072K2L"))
      (libsource (lib "eagle-import") (part "RESISTOR0603"))
    )
    (comp (ref "R12")
      (value "10k")
      (footprint "eagle-import:0603")
      (fields (field (name "PARTNO") "RC0603JR-0710KL"))
      (libsource (lib "eagle-import") (part "RESISTOR0603"))
    )
    (comp (ref "U7")
      (value "AFT05MS003NT1")
      (footprint "eagle-import:SOT-89")
      (libsource (lib "eagle-import") (part "AFT0SMS003N"))
    )
  )
  (nets
    (net (code "1") (name "3.3V") (class "Default")
      (node (ref "3V3") (pin "TP") (pinfunction "TP_TP") (pintype "input"))
      (node (ref "C14") (pin "P$1") (pinfunction "1_P$1") (pintype "passive"))
      (node (ref "C15") (pin "P$1") (pinfunction "1_P$1") (pintype "passive"))
      (node (ref "C16") (pin "P$1") (pinfunction "1_P$1") (pintype "passive"))
      (node (ref "C17") (pin "P$1") (pinfunction "1_P$1") (pintype "passive"))
      (node (ref "C26") (pin "P$1") (pinfunction "1_P$1") (pintype "passive"))
      (node (ref "C28") (pin "P$1") (pinfunction "1_P$1") (pintype "passive"))
      (node (ref "C3") (pin "P$1") (pinfunction "1_P$1") (pintype "passive"))
      (node (ref "C32") (pin "P$1") (pinfunction "1_P$1") (pintype "passive"))
      (node (ref "C34") (pin "P$1") (pinfunction "1_P$1") (pintype "passive"))
      (node (ref "C5") (pin "P$1") (pinfunction "1_P$1") (pintype "passive"))
      (node (ref "C6") (pin "P$1") (pinfunction "1_P$1") (pintype "passive"))
      (node (ref "JLINK") (pin "5") (pinfunction "5_5") (pintype "passive"))
      (node (ref "L12") (pin "P$2") (pinfunction "2_P$2") (pintype "passive"))
      (node (ref "R21") (pin "P$2") (pinfunction "P$2_P$2") (pintype "passive"))
      (node (ref "R22") (pin "P$2") (pinfunction "P$2_P$2") (pintype "passive"))
      (node (ref "U11") (pin "6") (pinfunction "VDD_1_6") (pintype "power_in"))
      (node (ref "U11") (pin "8") (pinfunction "VDD_2_8") (pintype "power_in"))
      (node (ref "U12") (pin "6") (pinfunction "VDD_1_6") (pintype "power_in"))
      (node (ref "U12") (pin "8") (pinfunction "VDD_2_8") (pintype "power_in"))
      (node (ref "U13") (pin "1") (pinfunction "VDD_1") (pintype "bidirectional"))
      (node (ref "U13") (pin "17") (pinfunction "VDD_17") (pintype "bidirectional"))
      (node (ref "U13") (pin "5") (pinfunction "VDDA_5") (pintype "bidirectional"))
      (node (ref "U2") (pin "P$6") (pinfunction "VBAT_P$6") (pintype "bidirectional"))
      (node (ref "U2") (pin "P$8") (pinfunction "VCC_P$8") (pintype "bidirectional"))
      (node (ref "U4") (pin "1") (pinfunction "VDD_1") (pintype "power_in"))
      (node (ref "U8") (pin "4") (pinfunction "VDD_4") (pintype "bidirectional"))
    )
    (net (code "2") (name "BOOT0") (class "Default")
      (node (ref "BOOT0") (pin "TP") (pinfunction "TP_TP") (pintype "input"))
      (node (ref "R23") (pin "P$1") (pinfunction "P$1_P$1") (pintype "passive"))
      (node (ref "U13") (pin "31") (pinfunction "BOOT0_31") (pintype "bidirectional"))
    )
    (net (code "3") (name "CS1") (class "Default")
      (node (ref "U11") (pin "15") (pinfunction "NSEL_15") (pintype "input"))
      (node (ref "U13") (pin "10") (pinfunction "PA4_10") (pintype "bidirectional"))
    )
    (net (code "4") (name "CS2") (class "Default")
      (node (ref "U12") (pin "15") (pinfunction "NSEL_15") (pintype "input"))
      (node (ref "U13") (pin "6") (pinfunction "PA0_6") (pintype "bidirectional"))
    )
    (net (code "5") (name "GND") (class "Default")
      (node (ref "C1") (pin "P$2") (pinfunction "2_P$2") (pintype "passive"))
      (node (ref "C11") (pin "P$2") (pinfunction "2_P$2") (pintype "passive"))
      (node (ref "C13") (pin "P$2") (pinfunction "2_P$2") (pintype "passive"))
      (node (ref "C14") (pin "P$2") (pinfunction "2_P$2") (pintype "passive"))
      (node (ref "C15") (pin "P$2") (pinfunction "2_P$2") (pintype "passive"))
      (node (ref "C16") (pin "P$2") (pinfunction "2_P$2") (pintype "passive"))
      (node (ref "C17") (pin "P$2") (pinfunction "2_P$2") (pintype "passive"))
      (node (ref "C21") (pin "P$2") (pinfunction "2_P$2") (pintype "passive"))
      (node (ref "C23") (pin "P$2") (pinfunction "2_P$2") (pintype "passive"))
      (node (ref "C26") (pin "P$2") (pinfunction "2_P$2") (pintype "passive"))
      (node (ref "C28") (pin "P$2") (pinfunction "2_P$2") (pintype "passive"))
      (node (ref "C3") (pin "P$2") (pinfunction "2_P$2") (pintype "passive"))
      (node (ref "C30") (pin "P$2") (pinfunction "2_P$2") (pintype "passive"))
      (node (ref "C32") (pin "P$2") (pinfunction "2_P$2") (pintype "passive"))
      (node (ref "C34") (pin "P$2") (pinfunction "2_P$2") (pintype "passive"))
      (node (ref "C36") (pin "P$2") (pinfunction "2_P$2") (pintype "passive"))
      (node (ref "C37") (pin "P$2") (pinfunction "2_P$2") (pintype "passive"))
      (node (ref "C39") (pin "P$2") (pinfunction "2_P$2") (pintype "passive"))
      (node (ref "C4") (pin "P$2") (pinfunction "2_P$2") (pintype "passive"))
      (node (ref "C42") (pin "P$2") (pinfunction "2_P$2") (pintype "passive"))
      (node (ref "C43") (pin "P$2") (pinfunction "2_P$2") (pintype "passive"))
      (node (ref "C47") (pin "P$2") (pinfunction "2_P$2") (pintype "passive"))
      (node (ref "C49") (pin "P$2") (pinfunction "2_P$2") (pintype "passive"))
      (node (ref "C5") (pin "P$2") (pinfunction "2_P$2") (pintype "passive"))
      (node (ref "C52") (pin "P$2") (pinfunction "2_P$2") (pintype "passive"))
      (node (ref "C53") (pin "P$2") (pinfunction "2_P$2") (pintype "passive"))
      (node (ref "C6") (pin "P$2") (pinfunction "2_P$2") (pintype "passive"))
      (node (ref "C7") (pin "P$2") (pinfunction "2_P$2") (pintype "passive"))
      (node (ref "C8") (pin "P$2") (pinfunction "2_P$2") (pintype "passive"))
      (node (ref "D3") (pin "C") (pinfunction "P$2_C") (pintype "bidirectional"))
      (node (ref "D4") (pin "A") (pinfunction "A_A") (pintype "passive"))
      (node (ref "GND1") (pin "TP") (pinfunction "TP_TP") (pintype "input"))
      (node (ref "GND2") (pin "TP") (pinfunction "TP_TP") (pintype "input"))
      (node (ref "J$1") (pin "GND@0") (pinfunction "GND_GND@0") (pintype "bidirectional"))
      (node (ref "J$1") (pin "GND@1") (pinfunction "GND_GND@1") (pintype "bidirectional"))
      (node (ref "J$1") (pin "GND@2") (pinfunction "GND_GND@2") (pintype "bidirectional"))
      (node (ref "J$1") (pin "GND@3") (pinfunction "GND_GND@3") (pintype "bidirectional"))
      (node (ref "JLINK") (pin "1") (pinfunction "1_1") (pintype "passive"))
      (node (ref "JP1") (pin "8") (pinfunction "8_8") (pintype "bidirectional"))
      (node (ref "L14") (pin "P$1") (pinfunction "1_P$1") (pintype "passive"))
      (node (ref "Q1") (pin "1") (pinfunction "G_1") (pintype "passive"))
      (node (ref "R12") (pin "P$1") (pinfunction "P$1_P$1") (pintype "passive"))
      (node (ref "R18") (pin "P$1") (pinfunction "P$1_P$1") (pintype "passive"))
      (node (ref "R23") (pin "P$2") (pinfunction "P$2_P$2") (pintype "passive"))
      (node (ref "R24") (pin "P$1") (pinfunction "P$1_P$1") (pintype "passive"))
      (node (ref "R4") (pin "P$1") (pinfunction "P$1_P$1") (pintype "passive"))
      (node (ref "S1") (pin "P$2") (pinfunction "S2_P$2") (pintype "bidirectional"))
      (node (ref "SWDIO1") (pin "TP") (pinfunction "TP_TP") (pintype "input"))
      (node (ref "SWDIO2") (pin "TP") (pinfunction "TP_TP") (pintype "input"))
      (node (ref "SWDIO3") (pin "TP") (pinfunction "TP_TP") (pintype "input"))
      (node (ref "SWDIO4") (pin "TP") (pinfunction "TP_TP") (pintype "input"))
      (node (ref "SWDIO5") (pin "TP") (pinfunction "TP_TP") (pintype "input"))
      (node (ref "SWDIO6") (pin "TP") (pinfunction "TP_TP") (pintype "input"))
      (node (ref "U1") (pin "2") (pinfunction "GND_2") (pintype "bidirectional"))
      (node (ref "U11") (pin "18") (pinfunction "GNDX_18") (pintype "bidirectional"))
      (node (ref "U11") (pin "3") (pinfunction "RXN_3") (pintype "input"))
      (node (ref "U11") (pin "5") (pinfunction "NC_5") (pintype "bidirectional"))
      (node (ref "U11") (pin "EXP") (pinfunction "PAD_EXP") (pintype "bidirectional"))
      (node (ref "U12") (pin "18") (pinfunction "GNDX_18") (pintype "bidirectional"))
      (node (ref "U12") (pin "3") (pinfunction "RXN_3") (pintype "input"))
      (node (ref "U12") (pin "5") (pinfunction "NC_5") (pintype "bidirectional"))
      (node (ref "U12") (pin "EXP") (pinfunction "PAD_EXP") (pintype "bidirectional"))
      (node (ref "U13") (pin "16") (pinfunction "VSS_16") (pintype "bidirectional"))
      (node (ref "U13") (pin "32") (pinfunction "VSS_32") (pintype "bidirectional"))
      (node (ref "U13") (pin "EXP") (pinfunction "PAD_EXP") (pintype "bidirectional"))
      (node (ref "U14") (pin "1") (pinfunction "S_1") (pintype "bidirectional"))
      (node (ref "U14") (pin "4") (pinfunction "S_4") (pintype "bidirectional"))
      (node (ref "U17") (pin "1") (pinfunction "S_1") (pintype "bidirectional"))
      (node (ref "U17") (pin "4") (pinfunction "S_4") (pintype "bidirectional"))
      (node (ref "U2") (pin "P$1") (pinfunction "GND_P$1") (pintype "bidirectional"))
      (node (ref "U2") (pin "P$10") (pinfunction "GND_P$10") (pintype "bidirectional"))
      (node (ref "U2") (pin "P$12") (pinfunction "GND_P$12") (pintype "bidirectional"))
      (node (ref "U3") (pin "P$4") (pinfunction "GND_P$4") (pintype "bidirectional"))
      (node (ref "U3") (pin "P$7") (pinfunction "GND_P$7") (pintype "bidirectional"))
      (node (ref "U4") (pin "7") (pinfunction "GND_7") (pintype "power_in"))
      (node (ref "U5") (pin "2") (pinfunction "GND_2") (pintype "bidirectional"))
      (node (ref "U5") (pin "4") (pinfunction "GND_4") (pintype "bidirectional"))
      (node (ref "U5") (pin "5") (pinfunction "GND_5") (pintype "bidirectional"))
      (node (ref "U6") (pin "3") (pinfunction "P$3_3") (pintype "bidirectional"))
      (node (ref "U7") (pin "2") (pinfunction "S_2") (pintype "passive"))
      (node (ref "U7") (pin "2@1") (pinfunction "PAD_2@1") (pintype "bidirectional"))
      (node (ref "U8") (pin "2") (pinfunction "GND_2") (pintype "bidirectional"))
      (node (ref "U9") (pin "P$3") (pinfunction "GND_P$3") (pintype "bidirectional"))
      (node (ref "X1") (pin "2") (pinfunction "G2_2") (pintype "power_in"))
      (node (ref "X1") (pin "4") (pinfunction "G1_4") (pintype "power_in"))
      (node (ref "X2") (pin "2") (pinfunction "G2_2") (pintype "power_in"))
      (node (ref "X2") (pin "4") (pinfunction "G1_4") (pintype "power_in"))
    )
    (net (code "6") (name "GPS_1PPS") (class "Default")
      (node (ref "U2") (pin "P$4") (pinfunction "1PPS_P$4") (pintype "bidirectional"))
      (node (ref "U4") (pin "3") (pinfunction "GPIO_1_3") (pintype "bidirectional"))
    )
    (net (code "7") (name "GPS_EN") (class "Default")
      (node (ref "U13") (pin "2") (pinfunction "OSC_IN/PC14_2") (pintype "bidirectional"))
      (node (ref "U4") (pin "2") (pinfunction "GPI_2") (pintype "input"))
    )
    (net (code "8") (name "GPS_STATUS") (class "Default")
      (node (ref "U13") (pin "21") (pinfunction "PA11_21") (pintype "bidirectional"))
      (node (ref "U14") (pin "5") (pinfunction "G_5") (pintype "bidirectional"))
    )
    (net (code "9") (name "GPS_UART_TX") (class "Default")
      (node (ref "U2") (pin "P$2") (pinfunction "TX_P$2") (pintype "bidirectional"))
      (node (ref "U4") (pin "4") (pinfunction "GPIO_2_4") (pintype "bidirectional"))
    )
    (net (code "10") (name "HOST_GPS_STATUS") (class "Default")
      (node (ref "JP1") (pin "4") (pinfunction "4_4") (pintype "bidirectional"))
      (node (ref "R14") (pin "P$2") (pinfunction "P$2_P$2") (pintype "passive"))
      (node (ref "U9") (pin "P$2") (pinfunction "C2_P$2") (pintype "bidirectional"))
    )
    (net (code "11") (name "HOST_RX_STATUS") (class "Default")
      (node (ref "JP1") (pin "6") (pinfunction "6_6") (pintype "bidirectional"))
      (node (ref "R15") (pin "P$2") (pinfunction "P$2_P$2") (pintype "passive"))
      (node (ref "U9") (pin "P$7") (pinfunction "C6_P$7") (pintype "bidirectional"))
    )
    (net (code "12") (name "HOST_TX_OFF") (class "Default")
      (node (ref "JP1") (pin "2") (pinfunction "2_2") (pintype "bidirectional"))
      (node (ref "R18") (pin "P$2") (pinfunction "P$2_P$2") (pintype "passive"))
      (node (ref "U17") (pin "2") (pinfunction "G_2") (pintype "bidirectional"))
      (node (ref "U9") (pin "P$1") (pinfunction "C1_P$1") (pintype "bidirectional"))
    )
    (net (code "13") (name "HOST_TX_STATUS") (class "Default")
      (node (ref "JP1") (pin "7") (pinfunction "7_7") (pintype "bidirectional"))
      (node (ref "R17") (pin "P$2") (pinfunction "P$2_P$2") (pintype "passive"))
      (node (ref "U9") (pin "P$6") (pinfunction "C5_P$6") (pintype "bidirectional"))
    )
    (net (code "14") (name "HOST_UART_RX") (class "Default")
      (node (ref "JP1") (pin "5") (pinfunction "5_5") (pintype "bidirectional"))
      (node (ref "R13") (pin "P$2") (pinfunction "P$2_P$2") (pintype "passive"))
      (node (ref "U9") (pin "P$8") (pinfunction "C7_P$8") (pintype "bidirectional"))
    )
    (net (code "15") (name "HOST_UART_TX") (class "Default")
      (node (ref "JP1") (pin "3") (pinfunction "3_3") (pintype "bidirectional"))
      (node (ref "R2") (pin "P$2") (pinfunction "P$2_P$2") (pintype "passive"))
      (node (ref "U9") (pin "P$9") (pinfunction "C8_P$9") (pintype "bidirectional"))
    )
    (net (code "16") (name "LNA_PWR") (class "Default")
      (node (ref "R10") (pin "P$1") (pinfunction "P$1_P$1") (pintype "passive"))
      (node (ref "U13") (pin "29") (pinfunction "PB6_29") (pintype "bidirectional"))
      (node (ref "V_LNA") (pin "TP") (pinfunction "TP_TP") (pintype "input"))
    )
    (net (code "17") (name "MCU_GPS_1PPS") (class "Default")
      (node (ref "U13") (pin "8") (pinfunction "PA2_8") (pintype "bidirectional"))
      (node (ref "U4") (pin "6") (pinfunction "GPIO_3_6") (pintype "bidirectional"))
    )
    (net (code "18") (name "MCU_GPS_UART_RX") (class "Default")
      (node (ref "U13") (pin "9") (pinfunction "PA3_9") (pintype "bidirectional"))
      (node (ref "U4") (pin "10") (pinfunction "GPIO_6_10") (pintype "bidirectional"))
    )
    (net (code "19") (name "MCU_TX_OFF") (class "Default")
      (node (ref "U13") (pin "22") (pinfunction "PA12_22") (pintype "bidirectional"))
      (node (ref "U17") (pin "6") (pinfunction "D_6") (pintype "bidirectional"))
    )
    (net (code "20") (name "MCU_UART_RX") (class "Default")
      (node (ref "R2") (pin "P$1") (pinfunction "P$1_P$1") (pintype "passive"))
      (node (ref "RX") (pin "TP") (pinfunction "TP_TP") (pintype "input"))
      (node (ref "U13") (pin "20") (pinfunction "PA10_20") (pintype "bidirectional"))
      (node (ref "U6") (pin "1") (pinfunction "P$1_1") (pintype "bidirectional"))
    )
    (net (code "21") (name "MCU_UART_TX") (class "Default")
      (node (ref "R13") (pin "P$1") (pinfunction "P$1_P$1") (pintype "passive"))
      (node (ref "TX") (pin "TP") (pinfunction "TP_TP") (pintype "input"))
      (node (ref "U13") (pin "19") (pinfunction "PA9_19") (pintype "bidirectional"))
      (node (ref "U6") (pin "2") (pinfunction "P$2_2") (pintype "bidirectional"))
    )
    (net (code "22") (name "MISO") (class "Default")
      (node (ref "U11") (pin "13") (pinfunction "SDO_13") (pintype "output"))
      (node (ref "U12") (pin "13") (pinfunction "SDO_13") (pintype "output"))
      (node (ref "U13") (pin "12") (pinfunction "PA6_12") (pintype "bidirectional"))
    )
    (net (code "23") (name "MOSI") (class "Default")
      (node (ref "U11") (pin "14") (pinfunction "SDI_14") (pintype "input"))
      (node (ref "U12") (pin "14") (pinfunction "SDI_14") (pintype "input"))
      (node (ref "U13") (pin "13") (pinfunction "PA7_13") (pintype "bidirectional"))
    )
    (net (code "24") (name "NRST") (class "Default")
      (node (ref "JLINK") (pin "2") (pinfunction "2_2") (pintype "passive"))
      (node (ref "NRST") (pin "TP") (pinfunction "TP_TP") (pintype "input"))
      (node (ref "S1") (pin "P$1") (pinfunction "S1_P$1") (pintype "bidirectional"))
      (node (ref "U13") (pin "4") (pinfunction "NRST_4") (pintype "bidirectional"))
    )
    (net (code "25") (name "Net-(C1-1)") (class "Default")
      (node (ref "C1") (pin "P$1") (pinfunction "1_P$1") (pintype "passive"))
      (node (ref "C43") (pin "P$1") (pinfunction "1_P$1") (pintype "passive"))
      (node (ref "L2") (pin "P$2") (pinfunction "2_P$2") (pintype "passive"))
      (node (ref "U1") (pin "4") (pinfunction "EN_4") (pintype "bidirectional"))
      (node (ref "U1") (pin "5") (pinfunction "IN_5") (pintype "bidirectional"))
    )
    (net (code "26") (name "Net-(C2-1)") (class "Default")
      (node (ref "C2") (pin "P$1") (pinfunction "1_P$1") (pintype "passive"))
      (node (ref "U1") (pin "1") (pinfunction "BS_1") (pintype "bidirectional"))
    )
    (net (code "27") (name "Net-(C2-2)") (class "Default")
      (node (ref "C2") (pin "P$2") (pinfunction "2_P$2") (pintype "passive"))
      (node (ref "D4") (pin "C") (pinfunction "C_C") (pintype "passive"))
      (node (ref "L12") (pin "P$1") (pinfunction "1_P$1") (pintype "passive"))
      (node (ref "U1") (pin "6") (pinfunction "SW_6") (pintype "bidirectional"))
    )
    (net (code "28") (name "Net-(C9-1)") (class "Default")
      (node (ref "C9") (pin "P$1") (pinfunction "1_P$1") (pintype "passive"))
      (node (ref "L8") (pin "P$2") (pinfunction "2_P$2") (pintype "passive"))
    )
    (net (code "29") (name "Net-(C10-1)") (class "Default")
      (node (ref "C10") (pin "P$1") (pinfunction "1_P$1") (pintype "passive"))
      (node (ref "C8") (pin "P$1") (pinfunction "1_P$1") (pintype "passive"))
      (node (ref "C9") (pin "P$2") (pinfunction "2_P$2") (pintype "passive"))
      (node (ref "L14") (pin "P$2") (pinfunction "2_P$2") (pintype "passive"))
    )
    (net (code "30") (name "Net-(C10-2)") (class "Default")
      (node (ref "C10") (pin "P$2") (pinfunction "2_P$2") (pintype "passive"))
      (node (ref "L13") (pin "P$1") (pinfunction "1_P$1") (pintype "passive"))
    )
    (net (code "31") (name "Net-(C12-1)") (class "Default")
      (node (ref "C12") (pin "P$1") (pinfunction "1_P$1") (pintype "passive"))
      (node (ref "L13") (pin "P$2") (pinfunction "2_P$2") (pintype "passive"))
    )
    (net (code "32") (name "Net-(C12-2)") (class "Default")
      (node (ref "C12") (pin "P$2") (pinfunction "2_P$2") (pintype "passive"))
      (node (ref "U5") (pin "6") (pinfunction "IN_6") (pintype "bidirectional"))
    )
    (net (code "33") (name "Net-(C13-1)") (class "Default")
      (node (ref "C13") (pin "P$1") (pinfunction "1_P$1") (pintype "passive"))
      (node (ref "R10") (pin "P$2") (pinfunction "P$2_P$2") (pintype "passive"))
      (node (ref "U5") (pin "1") (pinfunction "VCC_1") (pintype "bidirectional"))
    )
    (net (code "34") (name "Net-(C18-1)") (class "Default")
      (node (ref "C18") (pin "P$1") (pinfunction "1_P$1") (pintype "passive"))
      (node (ref "U5") (pin "3") (pinfunction "OUT_3") (pintype "bidirectional"))
    )
    (net (code "35") (name "Net-(C21-1)") (class "Default")
      (node (ref "C21") (pin "P$1") (pinfunction "1_P$1") (pintype "passive"))
      (node (ref "L5") (pin "P$1") (pinfunction "1_P$1") (pintype "passive"))
      (node (ref "R22") (pin "P$1") (pinfunction "P$1_P$1") (pintype "passive"))
    )
    (net (code "36") (name "Net-(C22-1)") (class "Default")
      (node (ref "C22") (pin "P$1") (pinfunction "1_P$1") (pintype "passive"))
      (node (ref "L5") (pin "P$2") (pinfunction "2_P$2") (pintype "passive"))
      (node (ref "U11") (pin "4") (pinfunction "TX_4") (pintype "output"))
    )
    (net (code "37") (name "Net-(C22-2)") (class "Default")
      (node (ref "C22") (pin "P$2") (pinfunction "2_P$2") (pintype "passive"))
      (node (ref "L1") (pin "P$1") (pinfunction "1_P$1") (pintype "passive"))
    )
    (net (code "38") (name "Net-(C23-1)") (class "Default")
      (node (ref "C23") (pin "P$1") (pinfunction "1_P$1") (pintype "passive"))
      (node (ref "L1") (pin "P$2") (pinfunction "2_P$2") (pintype "passive"))
      (node (ref "L6") (pin "P$1") (pinfunction "1_P$1") (pintype "passive"))
    )
    (net (code "39") (name "Net-(C29-2)") (class "Default")
      (node (ref "C29") (pin "P$2") (pinfunction "2_P$2") (pintype "passive"))
      (node (ref "C30") (pin "P$1") (pinfunction "1_P$1") (pintype "passive"))
      (node (ref "L3") (pin "P$1") (pinfunction "1_P$1") (pintype "passive"))
    )
    (net (code "40") (name "Net-(C36-1)") (class "Default")
      (node (ref "C36") (pin "P$1") (pinfunction "1_P$1") (pintype "passive"))
      (node (ref "L10") (pin "P$1") (pinfunction "1_P$1") (pintype "passive"))
      (node (ref "L9") (pin "P$2") (pinfunction "2_P$2") (pintype "passive"))
    )
    (net (code "41") (name "Net-(C37-1)") (class "Default")
      (node (ref "C37") (pin "P$1") (pinfunction "1_P$1") (pintype "passive"))
      (node (ref "C39") (pin "P$1") (pinfunction "1_P$1") (pintype "passive"))
      (node (ref "L4") (pin "P$2") (pinfunction "2_P$2") (pintype "passive"))
      (node (ref "L9") (pin "P$1") (pinfunction "1_P$1") (pintype "passive"))
      (node (ref "U7") (pin "3") (pinfunction "D_3") (pintype "passive"))
    )
    (net (code "42") (name "Net-(C42-1)") (class "Default")
      (node (ref "C42") (pin "P$1") (pinfunction "1_P$1") (pintype "passive"))
      (node (ref "C52") (pin "P$1") (pinfunction "1_P$1") (pintype "passive"))
      (node (ref "L10") (pin "P$2") (pinfunction "2_P$2") (pintype "passive"))
      (node (ref "L23") (pin "P$1") (pinfunction "1_P$1") (pintype "passive"))
    )
    (net (code "43") (name "Net-(C44-1)") (class "Default")
      (node (ref "C44") (pin "P$1") (pinfunction "1_P$1") (pintype "passive"))
      (node (ref "C53") (pin "P$1") (pinfunction "1_P$1") (pintype "passive"))
      (node (ref "L23") (pin "P$2") (pinfunction "2_P$2") (pintype "passive"))
    )
    (net (code "44") (name "Net-(J$1-SIGNAL)") (class "Default")
      (node (ref "J$1") (pin "SIG") (pinfunction "SIGNAL_SIG") (pintype "bidirectional"))
      (node (ref "RF") (pin "TP") (pinfunction "TP_TP") (pintype "input"))
      (node (ref "U8") (pin "5") (pinfunction "RFIN_5") (pintype "bidirectional"))
    )
    (net (code "45") (name "Net-(L17-1)") (class "Default")
      (node (ref "L17") (pin "P$1") (pinfunction "1_P$1") (pintype "passive"))
      (node (ref "L3") (pin "P$2") (pinfunction "2_P$2") (pintype "passive"))
      (node (ref "U7") (pin "1") (pinfunction "G_1") (pintype "passive"))
    )
    (net (code "46") (name "Net-(U1-FB)") (class "Default")
      (node (ref "R21") (pin "P$1") (pinfunction "P$1_P$1") (pintype "passive"))
      (node (ref "R24") (pin "P$2") (pinfunction "P$2_P$2") (pintype "passive"))
      (node (ref "U1") (pin "3") (pinfunction "FB_3") (pintype "bidirectional"))
    )
    (net (code "47") (name "Net-(U2-RFIN)") (class "Default")
      (node (ref "U2") (pin "P$11") (pinfunction "RFIN_P$11") (pintype "bidirectional"))
      (node (ref "Z1") (pin "P$2") (pinfunction "P$2_P$2") (pintype "passive"))
    )
    (net (code "48") (name "Net-(U3-ADJ)") (class "Default")
      (node (ref "R4") (pin "P$2") (pinfunction "P$2_P$2") (pintype "passive"))
      (node (ref "R5") (pin "P$1") (pinfunction "P$1_P$1") (pintype "passive"))
      (node (ref "U3") (pin "P$2") (pinfunction "ADJ_P$2") (pintype "bidirectional"))
    )
    (net (code "49") (name "Net-(U10-RF)") (class "Default")
      (node (ref "U10") (pin "P$1") (pinfunction "RF_P$1") (pintype "bidirectional"))
      (node (ref "Z1") (pin "P$1") (pinfunction "P$1_P$1") (pintype "passive"))
    )
    (net (code "50") (name "Net-(U11-XIN)") (class "Default")
      (node (ref "U11") (pin "17") (pinfunction "XIN_17") (pintype "input"))
      (node (ref "X1") (pin "3") (pinfunction "X2_3") (pintype "bidirectional"))
    )
    (net (code "51") (name "Net-(U11-XOUT)") (class "Default")
      (node (ref "U11") (pin "16") (pinfunction "XOUT_16") (pintype "bidirectional"))
      (node (ref "X1") (pin "1") (pinfunction "X1_1") (pintype "bidirectional"))
    )
    (net (code "52") (name "Net-(U12-XIN)") (class "Default")
      (node (ref "U12") (pin "17") (pinfunction "XIN_17") (pintype "input"))
      (node (ref "X2") (pin "3") (pinfunction "X2_3") (pintype "bidirectional"))
    )
    (net (code "53") (name "Net-(U12-XOUT)") (class "Default")
      (node (ref "U12") (pin "16") (pinfunction "XOUT_16") (pintype "bidirectional"))
      (node (ref "X2") (pin "1") (pinfunction "X1_1") (pintype "bidirectional"))
    )
    (net (code "54") (name "Net-(U14A-D)") (class "Default")
      (node (ref "R14") (pin "P$1") (pinfunction "P$1_P$1") (pintype "passive"))
      (node (ref "U14") (pin "3") (pinfunction "D_3") (pintype "bidirectional"))
    )
    (net (code "55") (name "Net-(U14B-D)") (class "Default")
      (node (ref "R15") (pin "P$1") (pinfunction "P$1_P$1") (pintype "passive"))
      (node (ref "U14") (pin "6") (pinfunction "D_6") (pintype "bidirectional"))
    )
    (net (code "56") (name "Net-(U17A-D)") (class "Default")
      (node (ref "R17") (pin "P$1") (pinfunction "P$1_P$1") (pintype "passive"))
      (node (ref "U17") (pin "3") (pinfunction "D_3") (pintype "bidirectional"))
    )
    (net (code "57") (name "PA_GATE_BIAS") (class "Default")
      (node (ref "C11") (pin "P$1") (pinfunction "1_P$1") (pintype "passive"))
      (node (ref "L17") (pin "P$2") (pinfunction "2_P$2") (pintype "passive"))
      (node (ref "R11") (pin "P$1") (pinfunction "P$1_P$1") (pintype "passive"))
      (node (ref "R12") (pin "P$2") (pinfunction "P$2_P$2") (pintype "passive"))
    )
    (net (code "58") (name "PA_IN") (class "Default")
      (node (ref "C29") (pin "P$1") (pinfunction "1_P$1") (pintype "passive"))
      (node (ref "L6") (pin "P$2") (pinfunction "2_P$2") (pintype "passive"))
    )
    (net (code "59") (name "PA_OUT") (class "Default")
      (node (ref "C44") (pin "P$2") (pinfunction "2_P$2") (pintype "passive"))
      (node (ref "U8") (pin "1") (pinfunction "RF2_1") (pintype "bidirectional"))
    )
    (net (code "60") (name "RFSW_CTRL") (class "Default")
      (node (ref "U13") (pin "30") (pinfunction "PB7_30") (pintype "bidirectional"))
      (node (ref "U8") (pin "6") (pinfunction "CTRL_6") (pintype "bidirectional"))
    )
    (net (code "61") (name "RF_IN") (class "Default")
      (node (ref "L8") (pin "P$1") (pinfunction "1_P$1") (pintype "passive"))
      (node (ref "U8") (pin "3") (pinfunction "RF1_3") (pintype "bidirectional"))
    )
    (net (code "62") (name "RX_IC_CLK") (class "Default")
      (node (ref "U12") (pin "20") (pinfunction "GPIO3_20") (pintype "bidirectional"))
      (node (ref "U13") (pin "26") (pinfunction "PB3_26") (pintype "bidirectional"))
    )
    (net (code "63") (name "RX_IC_DATA") (class "Default")
      (node (ref "U12") (pin "10") (pinfunction "GPIO1_10") (pintype "bidirectional"))
      (node (ref "U13") (pin "27") (pinfunction "PB4_27") (pintype "bidirectional"))
    )
    (net (code "64") (name "RX_IN") (class "Default")
      (node (ref "C18") (pin "P$2") (pinfunction "2_P$2") (pintype "passive"))
      (node (ref "U11") (pin "2") (pinfunction "RXP_2") (pintype "input"))
      (node (ref "U12") (pin "2") (pinfunction "RXP_2") (pintype "input"))
    )
    (net (code "65") (name "RX_STATUS") (class "Default")
      (node (ref "U13") (pin "7") (pinfunction "PA1_7") (pintype "bidirectional"))
      (node (ref "U14") (pin "2") (pinfunction "G_2") (pintype "bidirectional"))
    )
    (net (code "66") (name "SCK") (class "Default")
      (node (ref "U11") (pin "12") (pinfunction "SCLK_12") (pintype "input"))
      (node (ref "U12") (pin "12") (pinfunction "SCLK_12") (pintype "input"))
      (node (ref "U13") (pin "11") (pinfunction "PA5_11") (pintype "bidirectional"))
    )
    (net (code "67") (name "SDN1") (class "Default")
      (node (ref "U11") (pin "1") (pinfunction "SDN_1") (pintype "input"))
      (node (ref "U13") (pin "14") (pinfunction "PB0_14") (pintype "bidirectional"))
    )
    (net (code "68") (name "SDN2") (class "Default")
      (node (ref "U12") (pin "1") (pinfunction "SDN_1") (pintype "input"))
      (node (ref "U13") (pin "25") (pinfunction "PA15_25") (pintype "bidirectional"))
    )
    (net (code "69") (name "SWCLK") (class "Default")
      (node (ref "JLINK") (pin "3") (pinfunction "3_3") (pintype "passive"))
      (node (ref "SWCLK") (pin "TP") (pinfunction "TP_TP") (pintype "input"))
      (node (ref "U13") (pin "24") (pinfunction "PA14_24") (pintype "bidirectional"))
    )
    (net (code "70") (name "SWDIO") (class "Default")
      (node (ref "JLINK") (pin "4") (pinfunction "4_4") (pintype "passive"))
      (node (ref "SWDIO") (pin "TP") (pinfunction "TP_TP") (pintype "input"))
      (node (ref "U13") (pin "23") (pinfunction "PA13_23") (pintype "bidirectional"))
    )
    (net (code "71") (name "TRX_IC_CLOCK") (class "Default")
      (node (ref "U11") (pin "19") (pinfunction "GPIO2_19") (pintype "bidirectional"))
      (node (ref "U13") (pin "3") (pinfunction "OSC_OUT/PC15_3") (pintype "bidirectional"))
    )
    (net (code "72") (name "TRX_IC_DATA") (class "Default")
      (node (ref "U11") (pin "10") (pinfunction "GPIO1_10") (pintype "bidirectional"))
      (node (ref "U13") (pin "15") (pinfunction "PB1_15") (pintype "bidirectional"))
    )
    (net (code "73") (name "TX_STATUS") (class "Default")
      (node (ref "U13") (pin "28") (pinfunction "PB5_28") (pintype "bidirectional"))
      (node (ref "U17") (pin "5") (pinfunction "G_5") (pintype "bidirectional"))
    )
    (net (code "74") (name "V_IN") (class "Default")
      (node (ref "D3") (pin "A") (pinfunction "P$1_A") (pintype "bidirectional"))
      (node (ref "JP1") (pin "1") (pinfunction "1_1") (pintype "bidirectional"))
      (node (ref "Q1") (pin "3") (pinfunction "D_3") (pintype "passive"))
      (node (ref "V_IN") (pin "TP") (pinfunction "TP_TP") (pintype "input"))
    )
    (net (code "75") (name "V_PA") (class "Default")
      (node (ref "C49") (pin "P$1") (pinfunction "1_P$1") (pintype "passive"))
      (node (ref "C7") (pin "P$1") (pinfunction "1_P$1") (pintype "passive"))
      (node (ref "L4") (pin "P$1") (pinfunction "1_P$1") (pintype "passive"))
      (node (ref "R5") (pin "P$2") (pinfunction "P$2_P$2") (pintype "passive"))
      (node (ref "U3") (pin "P$1") (pinfunction "VOUT_P$1") (pintype "bidirectional"))
      (node (ref "V_PA") (pin "TP") (pinfunction "TP_TP") (pintype "input"))
    )
    (net (code "76") (name "V_PA_BIAS") (class "Default")
      (node (ref "R11") (pin "P$2") (pinfunction "P$2_P$2") (pintype "passive"))
      (node (ref "U13") (pin "18") (pinfunction "PA8_18") (pintype "bidirectional"))
    )
    (net (code "77") (name "V_PROT") (class "Default")
      (node (ref "C4") (pin "P$1") (pinfunction "1_P$1") (pintype "passive"))
      (node (ref "C47") (pin "P$1") (pinfunction "1_P$1") (pintype "passive"))
      (node (ref "L2") (pin "P$1") (pinfunction "1_P$1") (pintype "passive"))
      (node (ref "Q1") (pin "2") (pinfunction "S_2") (pintype "passive"))
      (node (ref "U3") (pin "P$5") (pinfunction "EN_P$5") (pintype "bidirectional"))
      (node (ref "U3") (pin "P$6") (pinfunction "VIN_P$6") (pintype "bidirectional"))
    )
    (net (code "78") (name "unconnected-(S1-S1-PadP$4)") (class "Default")
      (node (ref "S1") (pin "P$4") (pinfunction "S1_P$4") (pintype "bidirectional"))
    )
    (net (code "79") (name "unconnected-(S1-S2-PadP$3)") (class "Default")
      (node (ref "S1") (pin "P$3") (pinfunction "S2_P$3") (pintype "bidirectional"))
    )
    (net (code "80") (name "unconnected-(U2-RX-PadP$3)") (class "Default")
      (node (ref "U2") (pin "P$3") (pinfunction "RX_P$3") (pintype "bidirectional"))
    )
    (net (code "81") (name "unconnected-(U3-PG-PadP$3)") (class "Default")
      (node (ref "U3") (pin "P$3") (pinfunction "PG_P$3") (pintype "bidirectional"))
    )
    (net (code "82") (name "unconnected-(U4-GPIO_4-Pad8)") (class "Default")
      (node (ref "U4") (pin "8") (pinfunction "GPIO_4_8") (pintype "bidirectional"))
    )
    (net (code "83") (name "unconnected-(U4-GPIO_5-Pad9)") (class "Default")
      (node (ref "U4") (pin "9") (pinfunction "GPIO_5_9") (pintype "bidirectional"))
    )
    (net (code "84") (name "unconnected-(U4-GPIO_7-Pad12)") (class "Default")
      (node (ref "U4") (pin "12") (pinfunction "GPIO_7_12") (pintype "bidirectional"))
    )
    (net (code "85") (name "unconnected-(U4-NC_1-Pad5)") (class "Default")
      (node (ref "U4") (pin "5") (pinfunction "NC_1_5") (pintype "no_connect"))
    )
    (net (code "86") (name "unconnected-(U4-NC_2-Pad11)") (class "Default")
      (node (ref "U4") (pin "11") (pinfunction "NC_2_11") (pintype "no_connect"))
    )
    (net (code "87") (name "unconnected-(U9-C3-PadP$4)") (class "Default")
      (node (ref "U9") (pin "P$4") (pinfunction "C3_P$4") (pintype "bidirectional"))
    )
    (net (code "88") (name "unconnected-(U9-C4-PadP$5)") (class "Default")
      (node (ref "U9") (pin "P$5") (pinfunction "C4_P$5") (pintype "bidirectional"))
    )
    (net (code "89") (name "unconnected-(U10-PAD-PadP$2)") (class "Default")
      (node (ref "U10") (pin "P$2") (pinfunction "PAD_P$2") (pintype "bidirectional"))
    )
    (net (code "90") (name "unconnected-(U11-GPIO0-Pad9)") (class "Default")
      (node (ref "U11") (pin "9") (pinfunction "GPIO0_9") (pintype "bidirectional"))
    )
    (net (code "91") (name "unconnected-(U11-GPIO3-Pad20)") (class "Default")
      (node (ref "U11") (pin "20") (pinfunction "GPIO3_20") (pintype "bidirectional"))
    )
    (net (code "92") (name "unconnected-(U11-NIRQ-Pad11)") (class "Default")
      (node (ref "U11") (pin "11") (pinfunction "NIRQ_11") (pintype "bidirectional"))
    )
    (net (code "93") (name "unconnected-(U11-TXRAMP-Pad7)") (class "Default")
      (node (ref "U11") (pin "7") (pinfunction "TXRAMP_7") (pintype "bidirectional"))
    )
    (net (code "94") (name "unconnected-(U12-GPIO0-Pad9)") (class "Default")
      (node (ref "U12") (pin "9") (pinfunction "GPIO0_9") (pintype "bidirectional"))
    )
    (net (code "95") (name "unconnected-(U12-GPIO2-Pad19)") (class "Default")
      (node (ref "U12") (pin "19") (pinfunction "GPIO2_19") (pintype "bidirectional"))
    )
    (net (code "96") (name "unconnected-(U12-NIRQ-Pad11)") (class "Default")
      (node (ref "U12") (pin "11") (pinfunction "NIRQ_11") (pintype "bidirectional"))
    )
    (net (code "97") (name "unconnected-(U12-TX-Pad4)") (class "Default")
      (node (ref "U12") (pin "4") (pinfunction "TX_4") (pintype "output"))
    )
    (net (code "98") (name "unconnected-(U12-TXRAMP-Pad7)") (class "Default")
      (node (ref "U12") (pin "7") (pinfunction "TXRAMP_7") (pintype "bidirectional"))
    )
  )
)
